# CAN_Optical.net
KiCad netlist of a schematic drawn in Altium Designer
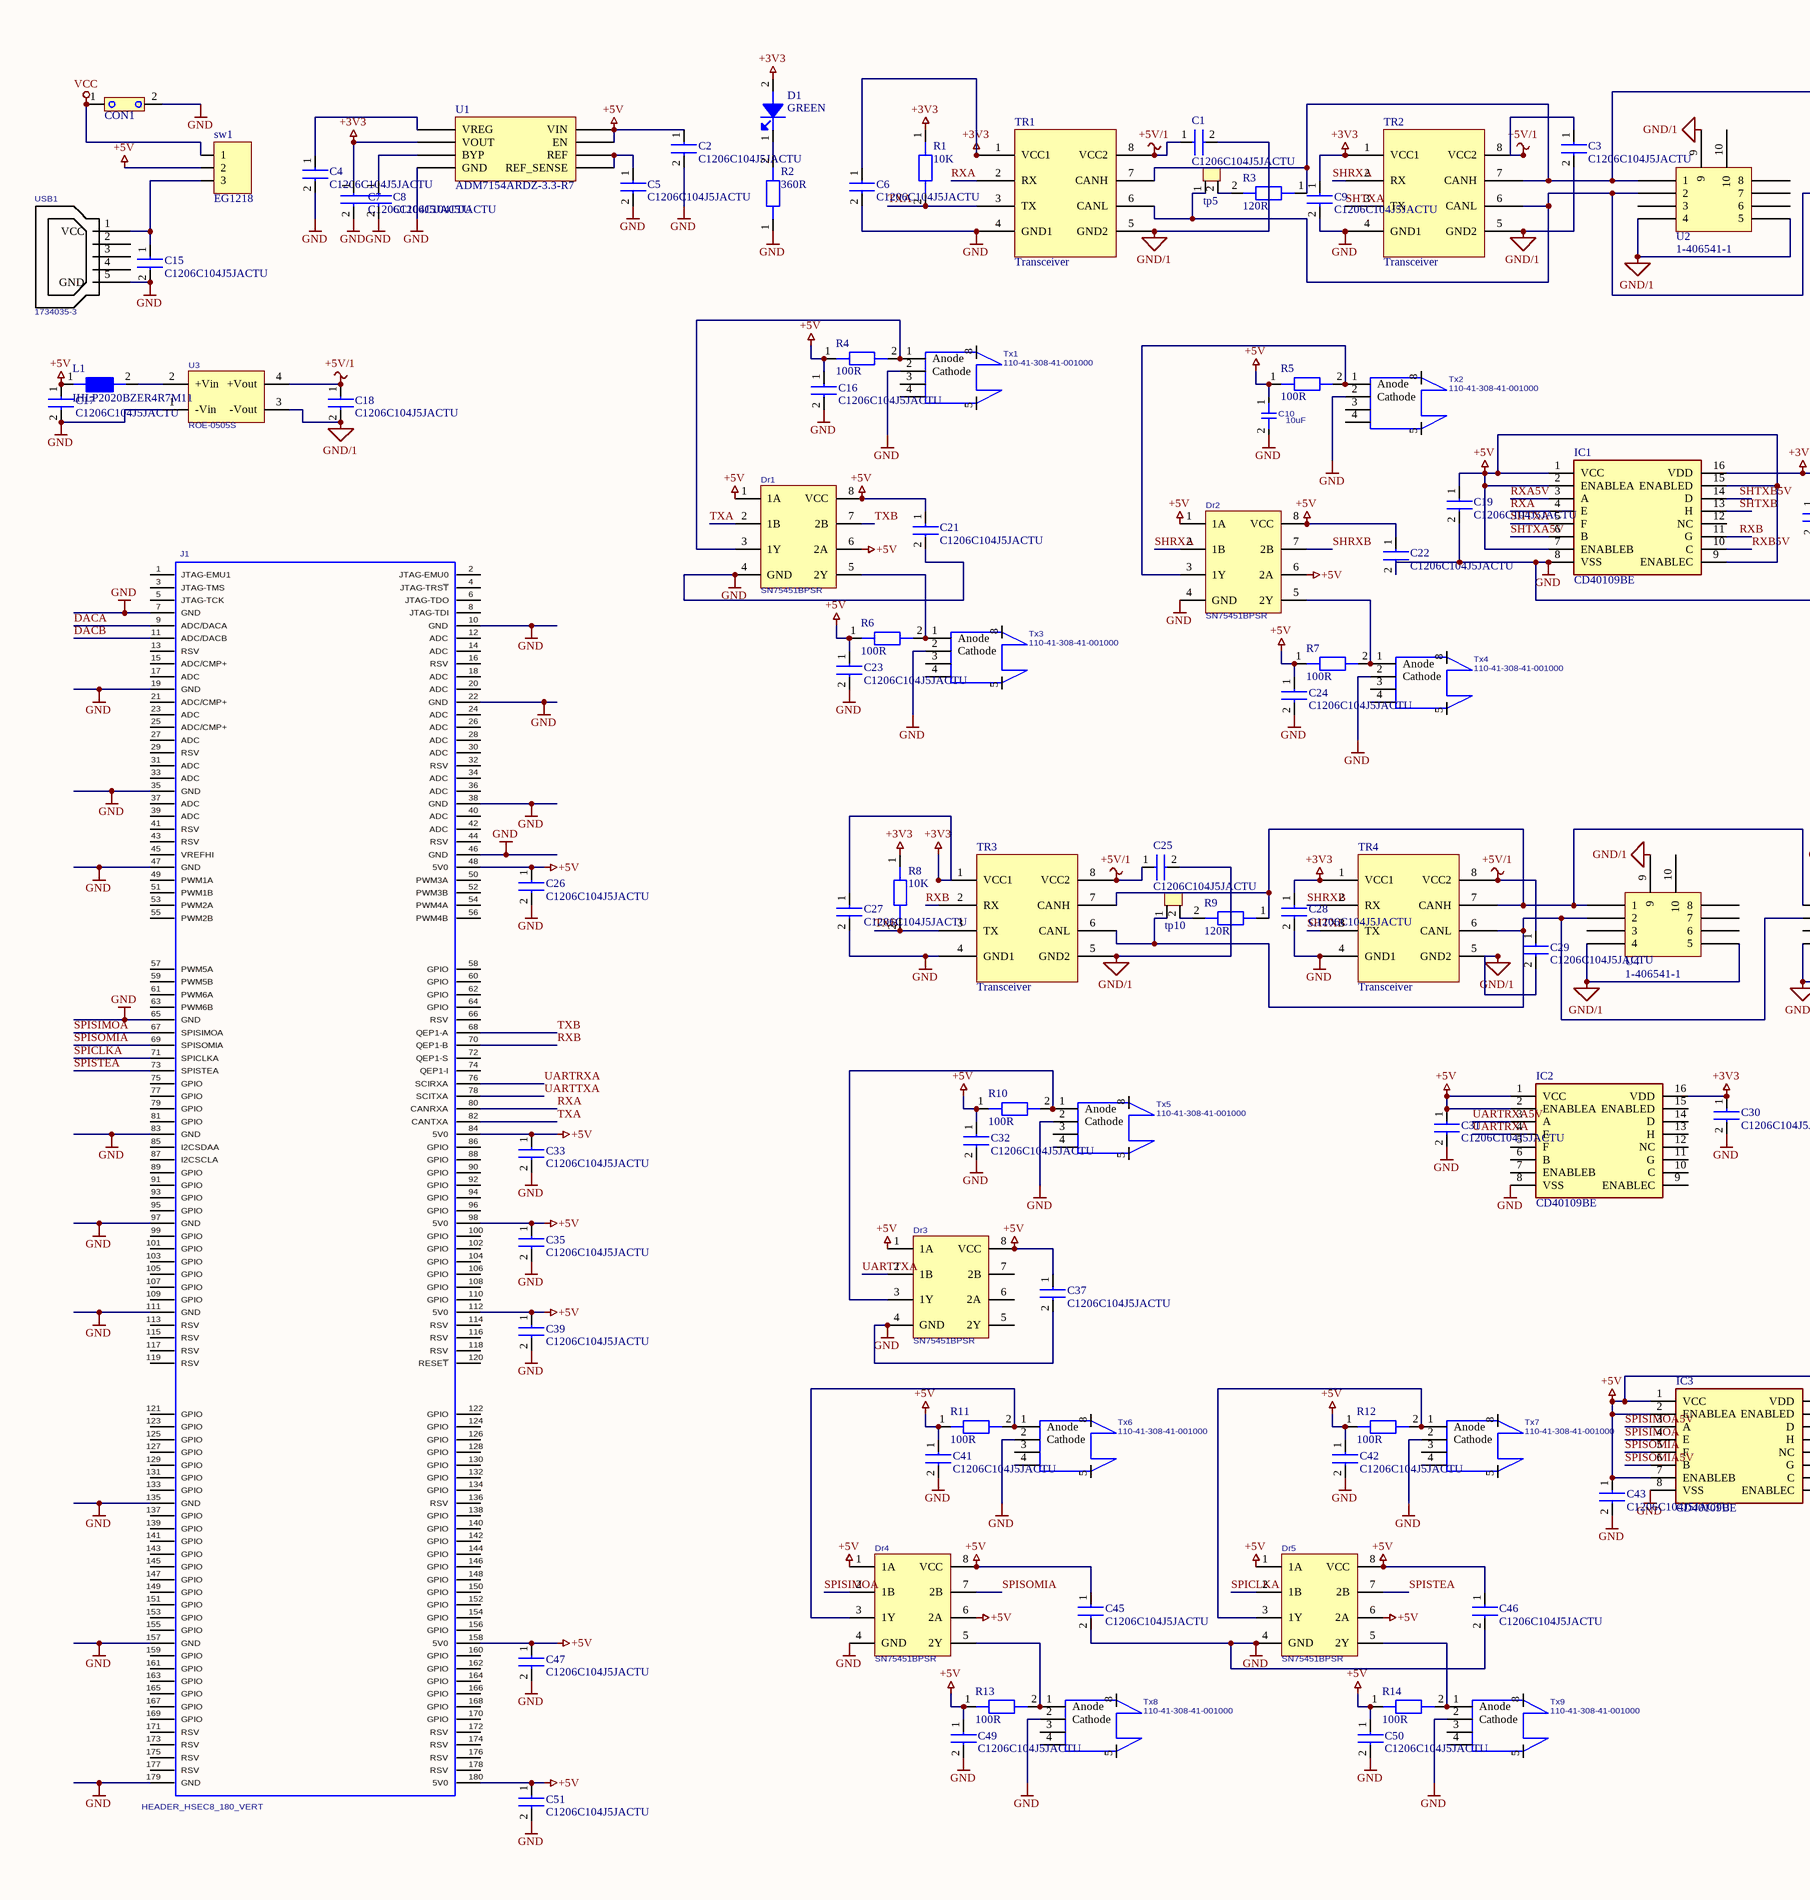
[diagram p0: CAN_Optical.SchDoc, left]
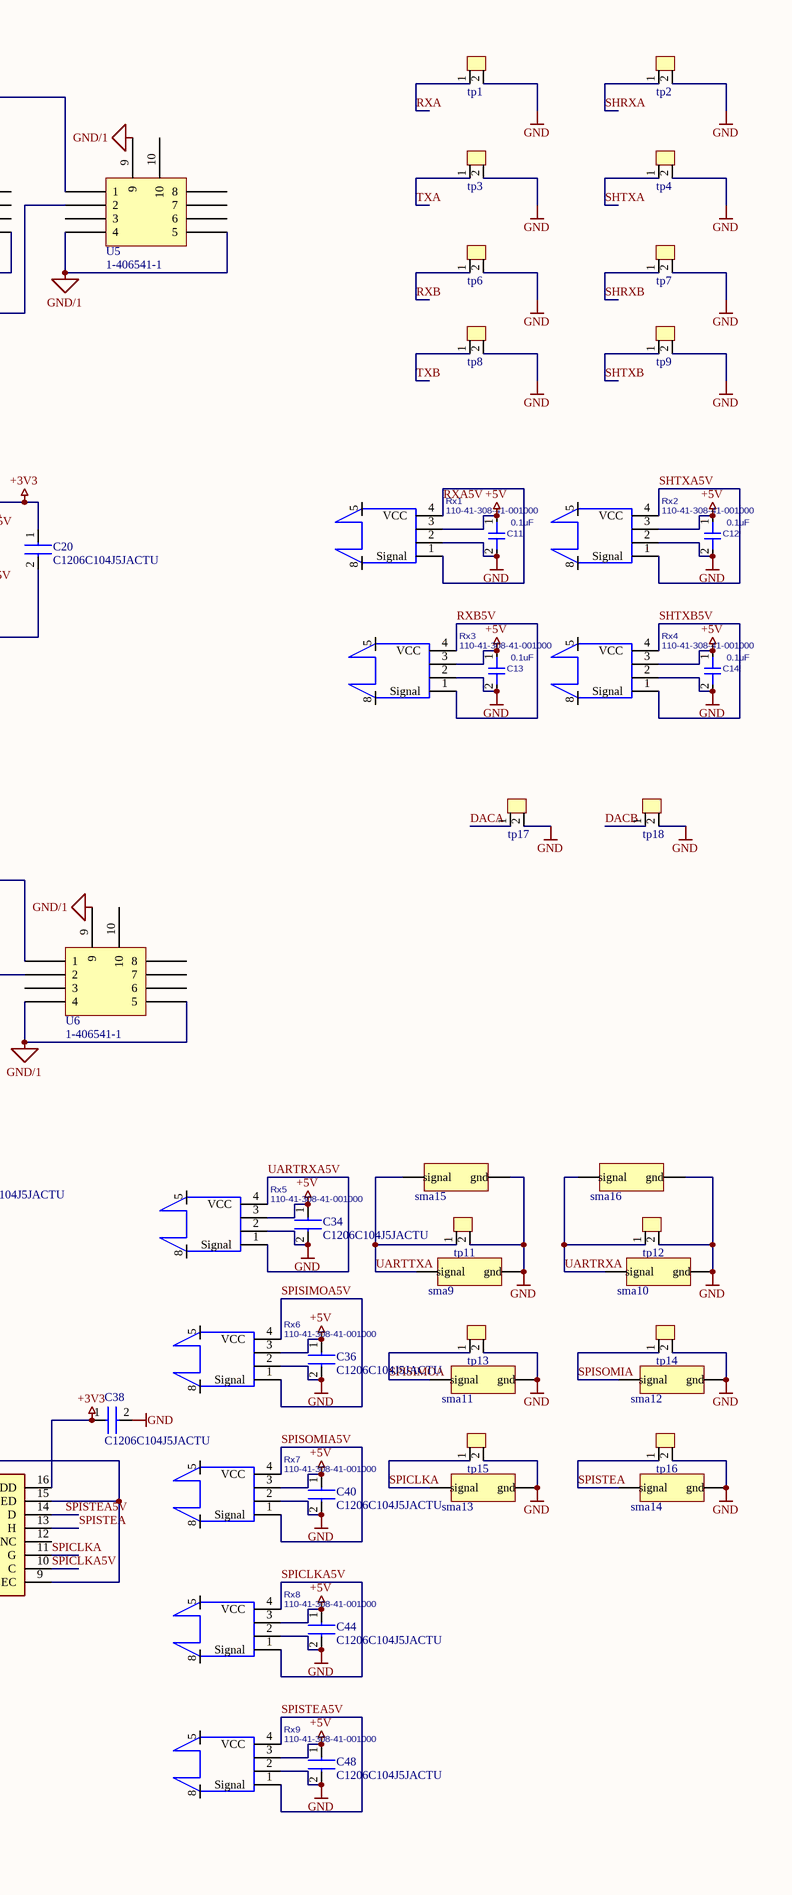
[diagram p1: CAN_Optical.SchDoc, right]

(export (version "E")
  (design (tool "Eeschema 10.0.6"))
  (components
    (comp (ref "C1")
      (value "C1206C104J5JACTU")
      (footprint "SamacSys:CAPC3216X135N")
      (description "Capacitor")
      (libsource (lib "CAN_Optical_SchLib") (part "C1206C104J5JACTU"))
    )
    (comp (ref "C2")
      (value "C1206C104J5JACTU")
      (footprint "SamacSys:CAPC3216X135N")
      (description "Capacitor")
      (libsource (lib "CAN_Optical_SchLib") (part "C1206C104J5JACTU"))
    )
    (comp (ref "C3")
      (value "C1206C104J5JACTU")
      (footprint "SamacSys:CAPC3216X135N")
      (description "Capacitor")
      (libsource (lib "CAN_Optical_SchLib") (part "C1206C104J5JACTU"))
    )
    (comp (ref "C4")
      (value "C1206C104J5JACTU")
      (footprint "SamacSys:CAPC3216X135N")
      (description "Capacitor")
      (libsource (lib "CAN_Optical_SchLib") (part "C1206C104J5JACTU"))
    )
    (comp (ref "C5")
      (value "C1206C104J5JACTU")
      (footprint "SamacSys:CAPC3216X135N")
      (description "Capacitor")
      (libsource (lib "CAN_Optical_SchLib") (part "C1206C104J5JACTU"))
    )
    (comp (ref "C6")
      (value "C1206C104J5JACTU")
      (footprint "SamacSys:CAPC3216X135N")
      (description "Capacitor")
      (libsource (lib "CAN_Optical_SchLib") (part "C1206C104J5JACTU"))
    )
    (comp (ref "C7")
      (value "C1206C104J5JACTU")
      (footprint "SamacSys:CAPC3216X135N")
      (description "Capacitor")
      (libsource (lib "CAN_Optical_SchLib") (part "C1206C104J5JACTU"))
    )
    (comp (ref "C8")
      (value "C1206C104J5JACTU")
      (footprint "SamacSys:CAPC3216X135N")
      (description "Capacitor")
      (libsource (lib "CAN_Optical_SchLib") (part "C1206C104J5JACTU"))
    )
    (comp (ref "C9")
      (value "C1206C104J5JACTU")
      (footprint "SamacSys:CAPC3216X135N")
      (description "Capacitor")
      (libsource (lib "CAN_Optical_SchLib") (part "C1206C104J5JACTU"))
    )
    (comp (ref "C10")
      (value "10uF")
      (footprint "CAPC3216X135N")
      (fields
        (field (name "MANUFACTURER") "KEMET")
        (field (name "MANUFACTURER PART NUMBER") "C0603C104K8RACTU")
        (field (name "TOLERANCE") "10%")
      )
      (libsource (lib "CAN_Optical_SchLib") (part "C0603C104K8RACTU"))
    )
    (comp (ref "C11")
      (value "0.1uF")
      (footprint "CAPC3216X135N")
      (fields
        (field (name "MANUFACTURER") "KEMET")
        (field (name "MANUFACTURER PART NUMBER") "C0603C104K8RACTU")
        (field (name "TOLERANCE") "10%")
      )
      (libsource (lib "CAN_Optical_SchLib") (part "C0603C104K8RACTU"))
    )
    (comp (ref "C12")
      (value "0.1uF")
      (footprint "CAPC3216X135N")
      (fields
        (field (name "MANUFACTURER") "KEMET")
        (field (name "MANUFACTURER PART NUMBER") "C0603C104K8RACTU")
        (field (name "TOLERANCE") "10%")
      )
      (libsource (lib "CAN_Optical_SchLib") (part "C0603C104K8RACTU"))
    )
    (comp (ref "C13")
      (value "0.1uF")
      (footprint "CAPC3216X135N")
      (fields
        (field (name "MANUFACTURER") "KEMET")
        (field (name "MANUFACTURER PART NUMBER") "C0603C104K8RACTU")
        (field (name "TOLERANCE") "10%")
      )
      (libsource (lib "CAN_Optical_SchLib") (part "C0603C104K8RACTU"))
    )
    (comp (ref "C14")
      (value "0.1uF")
      (footprint "CAPC3216X135N")
      (fields
        (field (name "MANUFACTURER") "KEMET")
        (field (name "MANUFACTURER PART NUMBER") "C0603C104K8RACTU")
        (field (name "TOLERANCE") "10%")
      )
      (libsource (lib "CAN_Optical_SchLib") (part "C0603C104K8RACTU"))
    )
    (comp (ref "C15")
      (value "C1206C104J5JACTU")
      (footprint "SamacSys:CAPC3216X135N")
      (description "Capacitor")
      (libsource (lib "CAN_Optical_SchLib") (part "C1206C104J5JACTU"))
    )
    (comp (ref "C16")
      (value "C1206C104J5JACTU")
      (footprint "SamacSys:CAPC3216X135N")
      (description "Capacitor")
      (libsource (lib "CAN_Optical_SchLib") (part "C1206C104J5JACTU"))
    )
    (comp (ref "C17")
      (value "C1206C104J5JACTU")
      (footprint "SamacSys:CAPC3216X135N")
      (description "Capacitor")
      (libsource (lib "CAN_Optical_SchLib") (part "C1206C104J5JACTU"))
    )
    (comp (ref "C18")
      (value "C1206C104J5JACTU")
      (footprint "SamacSys:CAPC3216X135N")
      (description "Capacitor")
      (libsource (lib "CAN_Optical_SchLib") (part "C1206C104J5JACTU"))
    )
    (comp (ref "C19")
      (value "C1206C104J5JACTU")
      (footprint "SamacSys:CAPC3216X135N")
      (description "Capacitor")
      (libsource (lib "CAN_Optical_SchLib") (part "C1206C104J5JACTU"))
    )
    (comp (ref "C20")
      (value "C1206C104J5JACTU")
      (footprint "SamacSys:CAPC3216X135N")
      (description "Capacitor")
      (libsource (lib "CAN_Optical_SchLib") (part "C1206C104J5JACTU"))
    )
    (comp (ref "C21")
      (value "C1206C104J5JACTU")
      (footprint "SamacSys:CAPC3216X135N")
      (description "Capacitor")
      (libsource (lib "CAN_Optical_SchLib") (part "C1206C104J5JACTU"))
    )
    (comp (ref "C22")
      (value "C1206C104J5JACTU")
      (footprint "SamacSys:CAPC3216X135N")
      (description "Capacitor")
      (libsource (lib "CAN_Optical_SchLib") (part "C1206C104J5JACTU"))
    )
    (comp (ref "C23")
      (value "C1206C104J5JACTU")
      (footprint "SamacSys:CAPC3216X135N")
      (description "Capacitor")
      (libsource (lib "CAN_Optical_SchLib") (part "C1206C104J5JACTU"))
    )
    (comp (ref "C24")
      (value "C1206C104J5JACTU")
      (footprint "SamacSys:CAPC3216X135N")
      (description "Capacitor")
      (libsource (lib "CAN_Optical_SchLib") (part "C1206C104J5JACTU"))
    )
    (comp (ref "C25")
      (value "C1206C104J5JACTU")
      (footprint "SamacSys:CAPC3216X135N")
      (description "Capacitor")
      (libsource (lib "CAN_Optical_SchLib") (part "C1206C104J5JACTU"))
    )
    (comp (ref "C26")
      (value "C1206C104J5JACTU")
      (footprint "SamacSys:CAPC3216X135N")
      (description "Capacitor")
      (libsource (lib "CAN_Optical_SchLib") (part "C1206C104J5JACTU"))
    )
    (comp (ref "C27")
      (value "C1206C104J5JACTU")
      (footprint "SamacSys:CAPC3216X135N")
      (description "Capacitor")
      (libsource (lib "CAN_Optical_SchLib") (part "C1206C104J5JACTU"))
    )
    (comp (ref "C28")
      (value "C1206C104J5JACTU")
      (footprint "SamacSys:CAPC3216X135N")
      (description "Capacitor")
      (libsource (lib "CAN_Optical_SchLib") (part "C1206C104J5JACTU"))
    )
    (comp (ref "C29")
      (value "C1206C104J5JACTU")
      (footprint "SamacSys:CAPC3216X135N")
      (description "Capacitor")
      (libsource (lib "CAN_Optical_SchLib") (part "C1206C104J5JACTU"))
    )
    (comp (ref "C30")
      (value "C1206C104J5JACTU")
      (footprint "SamacSys:CAPC3216X135N")
      (description "Capacitor")
      (libsource (lib "CAN_Optical_SchLib") (part "C1206C104J5JACTU"))
    )
    (comp (ref "C31")
      (value "C1206C104J5JACTU")
      (footprint "SamacSys:CAPC3216X135N")
      (description "Capacitor")
      (libsource (lib "CAN_Optical_SchLib") (part "C1206C104J5JACTU"))
    )
    (comp (ref "C32")
      (value "C1206C104J5JACTU")
      (footprint "SamacSys:CAPC3216X135N")
      (description "Capacitor")
      (libsource (lib "CAN_Optical_SchLib") (part "C1206C104J5JACTU"))
    )
    (comp (ref "C33")
      (value "C1206C104J5JACTU")
      (footprint "SamacSys:CAPC3216X135N")
      (description "Capacitor")
      (libsource (lib "CAN_Optical_SchLib") (part "C1206C104J5JACTU"))
    )
    (comp (ref "C34")
      (value "C1206C104J5JACTU")
      (footprint "SamacSys:CAPC3216X135N")
      (description "Capacitor")
      (libsource (lib "CAN_Optical_SchLib") (part "C1206C104J5JACTU"))
    )
    (comp (ref "C35")
      (value "C1206C104J5JACTU")
      (footprint "SamacSys:CAPC3216X135N")
      (description "Capacitor")
      (libsource (lib "CAN_Optical_SchLib") (part "C1206C104J5JACTU"))
    )
    (comp (ref "C36")
      (value "C1206C104J5JACTU")
      (footprint "SamacSys:CAPC3216X135N")
      (description "Capacitor")
      (libsource (lib "CAN_Optical_SchLib") (part "C1206C104J5JACTU"))
    )
    (comp (ref "C37")
      (value "C1206C104J5JACTU")
      (footprint "SamacSys:CAPC3216X135N")
      (description "Capacitor")
      (libsource (lib "CAN_Optical_SchLib") (part "C1206C104J5JACTU"))
    )
    (comp (ref "C38")
      (value "C1206C104J5JACTU")
      (footprint "SamacSys:CAPC3216X135N")
      (description "Capacitor")
      (libsource (lib "CAN_Optical_SchLib") (part "C1206C104J5JACTU"))
    )
    (comp (ref "C39")
      (value "C1206C104J5JACTU")
      (footprint "SamacSys:CAPC3216X135N")
      (description "Capacitor")
      (libsource (lib "CAN_Optical_SchLib") (part "C1206C104J5JACTU"))
    )
    (comp (ref "C40")
      (value "C1206C104J5JACTU")
      (footprint "SamacSys:CAPC3216X135N")
      (description "Capacitor")
      (libsource (lib "CAN_Optical_SchLib") (part "C1206C104J5JACTU"))
    )
    (comp (ref "C41")
      (value "C1206C104J5JACTU")
      (footprint "SamacSys:CAPC3216X135N")
      (description "Capacitor")
      (libsource (lib "CAN_Optical_SchLib") (part "C1206C104J5JACTU"))
    )
    (comp (ref "C42")
      (value "C1206C104J5JACTU")
      (footprint "SamacSys:CAPC3216X135N")
      (description "Capacitor")
      (libsource (lib "CAN_Optical_SchLib") (part "C1206C104J5JACTU"))
    )
    (comp (ref "C43")
      (value "C1206C104J5JACTU")
      (footprint "SamacSys:CAPC3216X135N")
      (description "Capacitor")
      (libsource (lib "CAN_Optical_SchLib") (part "C1206C104J5JACTU"))
    )
    (comp (ref "C44")
      (value "C1206C104J5JACTU")
      (footprint "SamacSys:CAPC3216X135N")
      (description "Capacitor")
      (libsource (lib "CAN_Optical_SchLib") (part "C1206C104J5JACTU"))
    )
    (comp (ref "C45")
      (value "C1206C104J5JACTU")
      (footprint "SamacSys:CAPC3216X135N")
      (description "Capacitor")
      (libsource (lib "CAN_Optical_SchLib") (part "C1206C104J5JACTU"))
    )
    (comp (ref "C46")
      (value "C1206C104J5JACTU")
      (footprint "SamacSys:CAPC3216X135N")
      (description "Capacitor")
      (libsource (lib "CAN_Optical_SchLib") (part "C1206C104J5JACTU"))
    )
    (comp (ref "C47")
      (value "C1206C104J5JACTU")
      (footprint "SamacSys:CAPC3216X135N")
      (description "Capacitor")
      (libsource (lib "CAN_Optical_SchLib") (part "C1206C104J5JACTU"))
    )
    (comp (ref "C48")
      (value "C1206C104J5JACTU")
      (footprint "SamacSys:CAPC3216X135N")
      (description "Capacitor")
      (libsource (lib "CAN_Optical_SchLib") (part "C1206C104J5JACTU"))
    )
    (comp (ref "C49")
      (value "C1206C104J5JACTU")
      (footprint "SamacSys:CAPC3216X135N")
      (description "Capacitor")
      (libsource (lib "CAN_Optical_SchLib") (part "C1206C104J5JACTU"))
    )
    (comp (ref "C50")
      (value "C1206C104J5JACTU")
      (footprint "SamacSys:CAPC3216X135N")
      (description "Capacitor")
      (libsource (lib "CAN_Optical_SchLib") (part "C1206C104J5JACTU"))
    )
    (comp (ref "C51")
      (value "C1206C104J5JACTU")
      (footprint "SamacSys:CAPC3216X135N")
      (description "Capacitor")
      (libsource (lib "CAN_Optical_SchLib") (part "C1206C104J5JACTU"))
    )
    (comp (ref "CON1")
      (value "ED700/2")
      (footprint "ED700/2")
      (fields (field (name "DIGI-KEY PART NUMBER") "ED1631-ND"))
      (libsource (lib "CAN_Optical_SchLib") (part "ED700/2"))
    )
    (comp (ref "D1")
      (value "GREEN")
      (footprint "LED0603G")
      (fields (field (name "TOLERANCE") "1%"))
      (libsource (lib "CAN_Optical_SchLib") (part "ERJ-3EKF8062V"))
    )
    (comp (ref "Dr1")
      (value "SN75451BPSR")
      (footprint "SN75451BPS")
      (description "IC DUAL PERIPHERAL DRVR 8-SOP")
      (fields (field (name "MANUFACTURER") "Texas Instruments"))
      (libsource (lib "CAN_Optical_SchLib") (part "SN75451BPSRG4"))
    )
    (comp (ref "Dr2")
      (value "SN75451BPSR")
      (footprint "SN75451BPS")
      (description "IC DUAL PERIPHERAL DRVR 8-SOP")
      (fields (field (name "MANUFACTURER") "Texas Instruments"))
      (libsource (lib "CAN_Optical_SchLib") (part "SN75451BPSR"))
    )
    (comp (ref "Dr3")
      (value "SN75451BPSR")
      (footprint "SN75451BPS")
      (description "IC DUAL PERIPHERAL DRVR 8-SOP")
      (fields (field (name "MANUFACTURER") "Texas Instruments"))
      (libsource (lib "CAN_Optical_SchLib") (part "SN75451BPSRG4"))
    )
    (comp (ref "Dr4")
      (value "SN75451BPSR")
      (footprint "SN75451BPS")
      (description "IC DUAL PERIPHERAL DRVR 8-SOP")
      (fields (field (name "MANUFACTURER") "Texas Instruments"))
      (libsource (lib "CAN_Optical_SchLib") (part "SN75451BPSRG4"))
    )
    (comp (ref "Dr5")
      (value "SN75451BPSR")
      (footprint "SN75451BPS")
      (description "IC DUAL PERIPHERAL DRVR 8-SOP")
      (fields (field (name "MANUFACTURER") "Texas Instruments"))
      (libsource (lib "CAN_Optical_SchLib") (part "SN75451BPSRG4"))
    )
    (comp (ref "IC1")
      (value "CD40109BE")
      (footprint "SamacSys:DIP794W53P254L1930H508Q16N")
      (description "Integrated Circuit")
      (fields (field (name "MOUSER2 PART NUMBER") "595-CD40109BE"))
      (libsource (lib "CAN_Optical_SchLib") (part "CD40109BE"))
    )
    (comp (ref "IC2")
      (value "CD40109BE")
      (footprint "SamacSys:DIP794W53P254L1930H508Q16N")
      (description "Integrated Circuit")
      (fields (field (name "MOUSER2 PART NUMBER") "595-CD40109BE"))
      (libsource (lib "CAN_Optical_SchLib") (part "CD40109BE"))
    )
    (comp (ref "IC3")
      (value "CD40109BE")
      (footprint "SamacSys:DIP794W53P254L1930H508Q16N")
      (description "Integrated Circuit")
      (fields (field (name "MOUSER2 PART NUMBER") "595-CD40109BE"))
      (libsource (lib "CAN_Optical_SchLib") (part "CD40109BE"))
    )
    (comp (ref "J1")
      (value "HEADER_HSEC8_180_VERT")
      (footprint "HEADER_HSEC8_180_DV")
      (description "180 pin (120 + 60) HSEC8 socket, samtec")
      (fields (field (name "DIGI-KEY PART NUMBER") "SAM9083-ND & SAM9080-ND"))
      (libsource (lib "CAN_Optical_SchLib") (part "HEADER_HSEC8_180_VERT"))
    )
    (comp (ref "L1")
      (value "IHLP2020BZER4R7M11")
      (footprint "L_IHLP2020BZER4R7M11")
      (description "FIXED IND 4.7UH 3.2A 81.3 MOHM")
      (fields (field (name "MANUFACTURER") "Vishay Dale") (field (name "TOLERANCE") "20%"))
      (libsource (lib "CAN_Optical_SchLib") (part "IHLP2020BZER4R7M11"))
    )
    (comp (ref "R1")
      (value "10K")
      (footprint "R0805 - duplicate - duplicate")
      (description "Res Thick Film 0805 360 Ohm 1% 0.125W(1/8W) ±100ppm/C Molded SMD Automotive Paper T/R")
      (fields (field (name "TOLERANCE") "1%"))
      (libsource (lib "CAN_Optical_SchLib") (part "CRCW0805360RFKEA"))
    )
    (comp (ref "R2")
      (value "360R")
      (footprint "R0805 - duplicate - duplicate")
      (description "Res Thick Film 0805 360 Ohm 1% 0.125W(1/8W) ±100ppm/C Molded SMD Automotive Paper T/R")
      (fields (field (name "TOLERANCE") "1%"))
      (libsource (lib "CAN_Optical_SchLib") (part "CRCW0805360RFKEA"))
    )
    (comp (ref "R3")
      (value "120R")
      (footprint "R0805 - duplicate - duplicate")
      (description "Res Thick Film 0805 360 Ohm 1% 0.125W(1/8W) ±100ppm/C Molded SMD Automotive Paper T/R")
      (fields (field (name "TOLERANCE") "1%"))
      (libsource (lib "CAN_Optical_SchLib") (part "CRCW0805360RFKEA"))
    )
    (comp (ref "R4")
      (value "100R")
      (footprint "R0805 - duplicate - duplicate")
      (description "Res Thick Film 0805 360 Ohm 1% 0.125W(1/8W) ±100ppm/C Molded SMD Automotive Paper T/R")
      (fields (field (name "TOLERANCE") "1%"))
      (libsource (lib "CAN_Optical_SchLib") (part "CRCW0805360RFKEA"))
    )
    (comp (ref "R5")
      (value "100R")
      (footprint "R0805 - duplicate - duplicate")
      (description "Res Thick Film 0805 360 Ohm 1% 0.125W(1/8W) ±100ppm/C Molded SMD Automotive Paper T/R")
      (fields (field (name "TOLERANCE") "1%"))
      (libsource (lib "CAN_Optical_SchLib") (part "CRCW0805360RFKEA"))
    )
    (comp (ref "R6")
      (value "100R")
      (footprint "R0805 - duplicate - duplicate")
      (description "Res Thick Film 0805 360 Ohm 1% 0.125W(1/8W) ±100ppm/C Molded SMD Automotive Paper T/R")
      (fields (field (name "TOLERANCE") "1%"))
      (libsource (lib "CAN_Optical_SchLib") (part "CRCW0805360RFKEA"))
    )
    (comp (ref "R7")
      (value "100R")
      (footprint "R0805 - duplicate - duplicate")
      (description "Res Thick Film 0805 360 Ohm 1% 0.125W(1/8W) ±100ppm/C Molded SMD Automotive Paper T/R")
      (fields (field (name "TOLERANCE") "1%"))
      (libsource (lib "CAN_Optical_SchLib") (part "CRCW0805360RFKEA"))
    )
    (comp (ref "R8")
      (value "10K")
      (footprint "R0805 - duplicate - duplicate")
      (description "Res Thick Film 0805 360 Ohm 1% 0.125W(1/8W) ±100ppm/C Molded SMD Automotive Paper T/R")
      (fields (field (name "TOLERANCE") "1%"))
      (libsource (lib "CAN_Optical_SchLib") (part "CRCW0805360RFKEA"))
    )
    (comp (ref "R9")
      (value "120R")
      (footprint "R0805 - duplicate - duplicate")
      (description "Res Thick Film 0805 360 Ohm 1% 0.125W(1/8W) ±100ppm/C Molded SMD Automotive Paper T/R")
      (fields (field (name "TOLERANCE") "1%"))
      (libsource (lib "CAN_Optical_SchLib") (part "CRCW0805360RFKEA"))
    )
    (comp (ref "R10")
      (value "100R")
      (footprint "R0805 - duplicate - duplicate")
      (description "Res Thick Film 0805 360 Ohm 1% 0.125W(1/8W) ±100ppm/C Molded SMD Automotive Paper T/R")
      (fields (field (name "TOLERANCE") "1%"))
      (libsource (lib "CAN_Optical_SchLib") (part "CRCW0805360RFKEA"))
    )
    (comp (ref "R11")
      (value "100R")
      (footprint "R0805 - duplicate - duplicate")
      (description "Res Thick Film 0805 360 Ohm 1% 0.125W(1/8W) ±100ppm/C Molded SMD Automotive Paper T/R")
      (fields (field (name "TOLERANCE") "1%"))
      (libsource (lib "CAN_Optical_SchLib") (part "CRCW0805360RFKEA"))
    )
    (comp (ref "R12")
      (value "100R")
      (footprint "R0805 - duplicate - duplicate")
      (description "Res Thick Film 0805 360 Ohm 1% 0.125W(1/8W) ±100ppm/C Molded SMD Automotive Paper T/R")
      (fields (field (name "TOLERANCE") "1%"))
      (libsource (lib "CAN_Optical_SchLib") (part "CRCW0805360RFKEA"))
    )
    (comp (ref "R13")
      (value "100R")
      (footprint "R0805 - duplicate - duplicate")
      (description "Res Thick Film 0805 360 Ohm 1% 0.125W(1/8W) ±100ppm/C Molded SMD Automotive Paper T/R")
      (fields (field (name "TOLERANCE") "1%"))
      (libsource (lib "CAN_Optical_SchLib") (part "CRCW0805360RFKEA"))
    )
    (comp (ref "R14")
      (value "100R")
      (footprint "R0805 - duplicate - duplicate")
      (description "Res Thick Film 0805 360 Ohm 1% 0.125W(1/8W) ±100ppm/C Molded SMD Automotive Paper T/R")
      (fields (field (name "TOLERANCE") "1%"))
      (libsource (lib "CAN_Optical_SchLib") (part "CRCW0805360RFKEA"))
    )
    (comp (ref "Rx1")
      (value "110-41-308-41-001000")
      (footprint "HFBRX5XXZ")
      (description "IC & Component Sockets 8 PIN SKT 200u Sn")
      (fields (field (name "MANUFACTURER") "Broadcom"))
      (libsource (lib "CAN_Optical_SchLib") (part "HFBR-2521Z"))
    )
    (comp (ref "Rx2")
      (value "110-41-308-41-001000")
      (footprint "HFBRX5XXZ")
      (description "IC & Component Sockets 8 PIN SKT 200u Sn")
      (fields (field (name "MANUFACTURER") "Broadcom"))
      (libsource (lib "CAN_Optical_SchLib") (part "HFBR-2521Z"))
    )
    (comp (ref "Rx3")
      (value "110-41-308-41-001000")
      (footprint "HFBRX5XXZ")
      (description "IC & Component Sockets 8 PIN SKT 200u Sn")
      (fields (field (name "MANUFACTURER") "Broadcom"))
      (libsource (lib "CAN_Optical_SchLib") (part "HFBR-2521Z"))
    )
    (comp (ref "Rx4")
      (value "110-41-308-41-001000")
      (footprint "HFBRX5XXZ")
      (description "IC & Component Sockets 8 PIN SKT 200u Sn")
      (fields (field (name "MANUFACTURER") "Broadcom"))
      (libsource (lib "CAN_Optical_SchLib") (part "HFBR-2521Z"))
    )
    (comp (ref "Rx5")
      (value "110-41-308-41-001000")
      (footprint "HFBRX5XXZ")
      (description "IC & Component Sockets 8 PIN SKT 200u Sn")
      (fields (field (name "MANUFACTURER") "Broadcom"))
      (libsource (lib "CAN_Optical_SchLib") (part "HFBR-2521Z"))
    )
    (comp (ref "Rx6")
      (value "110-41-308-41-001000")
      (footprint "HFBRX5XXZ")
      (description "IC & Component Sockets 8 PIN SKT 200u Sn")
      (fields (field (name "MANUFACTURER") "Broadcom"))
      (libsource (lib "CAN_Optical_SchLib") (part "HFBR-2521Z"))
    )
    (comp (ref "Rx7")
      (value "110-41-308-41-001000")
      (footprint "HFBRX5XXZ")
      (description "IC & Component Sockets 8 PIN SKT 200u Sn")
      (fields (field (name "MANUFACTURER") "Broadcom"))
      (libsource (lib "CAN_Optical_SchLib") (part "HFBR-2521Z"))
    )
    (comp (ref "Rx8")
      (value "110-41-308-41-001000")
      (footprint "HFBRX5XXZ")
      (description "IC & Component Sockets 8 PIN SKT 200u Sn")
      (fields (field (name "MANUFACTURER") "Broadcom"))
      (libsource (lib "CAN_Optical_SchLib") (part "HFBR-2521Z"))
    )
    (comp (ref "Rx9")
      (value "110-41-308-41-001000")
      (footprint "HFBRX5XXZ")
      (description "IC & Component Sockets 8 PIN SKT 200u Sn")
      (fields (field (name "MANUFACTURER") "Broadcom"))
      (libsource (lib "CAN_Optical_SchLib") (part "HFBR-2521Z"))
    )
    (comp (ref "sma9")
      (value "142-0701-201")
      (footprint "142-0701-201")
      (fields (field (name "DIGI-KEY PART NUMBER") "J500-ND"))
      (libsource (lib "CAN_Optical_SchLib") (part "142-0701-201"))
    )
    (comp (ref "sma10")
      (value "142-0701-201")
      (footprint "142-0701-201")
      (fields (field (name "DIGI-KEY PART NUMBER") "J500-ND"))
      (libsource (lib "CAN_Optical_SchLib") (part "142-0701-201"))
    )
    (comp (ref "sma11")
      (value "142-0701-201")
      (footprint "142-0701-201")
      (fields (field (name "DIGI-KEY PART NUMBER") "J500-ND"))
      (libsource (lib "CAN_Optical_SchLib") (part "142-0701-201"))
    )
    (comp (ref "sma12")
      (value "142-0701-201")
      (footprint "142-0701-201")
      (fields (field (name "DIGI-KEY PART NUMBER") "J500-ND"))
      (libsource (lib "CAN_Optical_SchLib") (part "142-0701-201"))
    )
    (comp (ref "sma13")
      (value "142-0701-201")
      (footprint "142-0701-201")
      (fields (field (name "DIGI-KEY PART NUMBER") "J500-ND"))
      (libsource (lib "CAN_Optical_SchLib") (part "142-0701-201"))
    )
    (comp (ref "sma14")
      (value "142-0701-201")
      (footprint "142-0701-201")
      (fields (field (name "DIGI-KEY PART NUMBER") "J500-ND"))
      (libsource (lib "CAN_Optical_SchLib") (part "142-0701-201"))
    )
    (comp (ref "sma15")
      (value "142-0701-201")
      (footprint "142-0701-201")
      (fields (field (name "DIGI-KEY PART NUMBER") "J500-ND"))
      (libsource (lib "CAN_Optical_SchLib") (part "142-0701-201"))
    )
    (comp (ref "sma16")
      (value "142-0701-201")
      (footprint "142-0701-201")
      (fields (field (name "DIGI-KEY PART NUMBER") "J500-ND"))
      (libsource (lib "CAN_Optical_SchLib") (part "142-0701-201"))
    )
    (comp (ref "sw1")
      (value "EG1218")
      (footprint "EG1218")
      (fields (field (name "DIGI-KEY PART NUMBER") "EG1903-ND"))
      (libsource (lib "CAN_Optical_SchLib") (part "EG1218"))
    )
    (comp (ref "tp1")
      (value "tp2")
      (footprint "tp2")
      (fields (field (name "DIGI-KEY PART NUMBER") "S1012EC-10-ND"))
      (libsource (lib "CAN_Optical_SchLib") (part "tp2"))
    )
    (comp (ref "tp2")
      (value "tp2")
      (footprint "tp2")
      (fields (field (name "DIGI-KEY PART NUMBER") "S1012EC-10-ND"))
      (libsource (lib "CAN_Optical_SchLib") (part "tp2"))
    )
    (comp (ref "tp3")
      (value "tp2")
      (footprint "tp2")
      (fields (field (name "DIGI-KEY PART NUMBER") "S1012EC-10-ND"))
      (libsource (lib "CAN_Optical_SchLib") (part "tp2"))
    )
    (comp (ref "tp4")
      (value "tp2")
      (footprint "tp2")
      (fields (field (name "DIGI-KEY PART NUMBER") "S1012EC-10-ND"))
      (libsource (lib "CAN_Optical_SchLib") (part "tp2"))
    )
    (comp (ref "tp5")
      (value "tp2")
      (footprint "tp2")
      (fields (field (name "DIGI-KEY PART NUMBER") "S1012EC-10-ND"))
      (libsource (lib "CAN_Optical_SchLib") (part "tp2"))
    )
    (comp (ref "tp6")
      (value "tp2")
      (footprint "tp2")
      (fields (field (name "DIGI-KEY PART NUMBER") "S1012EC-10-ND"))
      (libsource (lib "CAN_Optical_SchLib") (part "tp2"))
    )
    (comp (ref "tp7")
      (value "tp2")
      (footprint "tp2")
      (fields (field (name "DIGI-KEY PART NUMBER") "S1012EC-10-ND"))
      (libsource (lib "CAN_Optical_SchLib") (part "tp2"))
    )
    (comp (ref "tp8")
      (value "tp2")
      (footprint "tp2")
      (fields (field (name "DIGI-KEY PART NUMBER") "S1012EC-10-ND"))
      (libsource (lib "CAN_Optical_SchLib") (part "tp2"))
    )
    (comp (ref "tp9")
      (value "tp2")
      (footprint "tp2")
      (fields (field (name "DIGI-KEY PART NUMBER") "S1012EC-10-ND"))
      (libsource (lib "CAN_Optical_SchLib") (part "tp2"))
    )
    (comp (ref "tp10")
      (value "tp2")
      (footprint "tp2")
      (fields (field (name "DIGI-KEY PART NUMBER") "S1012EC-10-ND"))
      (libsource (lib "CAN_Optical_SchLib") (part "tp2"))
    )
    (comp (ref "tp11")
      (value "tp2")
      (footprint "tp2")
      (fields (field (name "DIGI-KEY PART NUMBER") "S1012EC-10-ND"))
      (libsource (lib "CAN_Optical_SchLib") (part "tp2"))
    )
    (comp (ref "tp12")
      (value "tp2")
      (footprint "tp2")
      (fields (field (name "DIGI-KEY PART NUMBER") "S1012EC-10-ND"))
      (libsource (lib "CAN_Optical_SchLib") (part "tp2"))
    )
    (comp (ref "tp13")
      (value "tp2")
      (footprint "tp2")
      (fields (field (name "DIGI-KEY PART NUMBER") "S1012EC-10-ND"))
      (libsource (lib "CAN_Optical_SchLib") (part "tp2"))
    )
    (comp (ref "tp14")
      (value "tp2")
      (footprint "tp2")
      (fields (field (name "DIGI-KEY PART NUMBER") "S1012EC-10-ND"))
      (libsource (lib "CAN_Optical_SchLib") (part "tp2"))
    )
    (comp (ref "tp15")
      (value "tp2")
      (footprint "tp2")
      (fields (field (name "DIGI-KEY PART NUMBER") "S1012EC-10-ND"))
      (libsource (lib "CAN_Optical_SchLib") (part "tp2"))
    )
    (comp (ref "tp16")
      (value "tp2")
      (footprint "tp2")
      (fields (field (name "DIGI-KEY PART NUMBER") "S1012EC-10-ND"))
      (libsource (lib "CAN_Optical_SchLib") (part "tp2"))
    )
    (comp (ref "tp17")
      (value "tp2")
      (footprint "tp2")
      (fields (field (name "DIGI-KEY PART NUMBER") "S1012EC-10-ND"))
      (libsource (lib "CAN_Optical_SchLib") (part "tp2"))
    )
    (comp (ref "tp18")
      (value "tp2")
      (footprint "tp2")
      (fields (field (name "DIGI-KEY PART NUMBER") "S1012EC-10-ND"))
      (libsource (lib "CAN_Optical_SchLib") (part "tp2"))
    )
    (comp (ref "TR1")
      (value "Transceiver")
      (footprint "RXTX_ISO1050")
      (description "CAN 1Mbps 3.3V/5V 8-Pin SOP")
      (fields
        (field (name "MANUFACTURER") "Texas Instruments")
        (field (name "MANUFACTURER PART NUMBER") "ISO1050DUBR")
      )
      (libsource (lib "CAN_Optical_SchLib") (part "ISO1050DUBR"))
    )
    (comp (ref "TR2")
      (value "Transceiver")
      (footprint "RXTX_ISO1050")
      (description "CAN 1Mbps 3.3V/5V 8-Pin SOP")
      (fields
        (field (name "MANUFACTURER") "Texas Instruments")
        (field (name "MANUFACTURER PART NUMBER") "ISO1050DUBR")
      )
      (libsource (lib "CAN_Optical_SchLib") (part "ISO1050DUBR"))
    )
    (comp (ref "TR3")
      (value "Transceiver")
      (footprint "RXTX_ISO1050")
      (description "CAN 1Mbps 3.3V/5V 8-Pin SOP")
      (fields
        (field (name "MANUFACTURER") "Texas Instruments")
        (field (name "MANUFACTURER PART NUMBER") "ISO1050DUBR")
      )
      (libsource (lib "CAN_Optical_SchLib") (part "ISO1050DUBR"))
    )
    (comp (ref "TR4")
      (value "Transceiver")
      (footprint "RXTX_ISO1050")
      (description "CAN 1Mbps 3.3V/5V 8-Pin SOP")
      (fields
        (field (name "MANUFACTURER") "Texas Instruments")
        (field (name "MANUFACTURER PART NUMBER") "ISO1050DUBR")
      )
      (libsource (lib "CAN_Optical_SchLib") (part "ISO1050DUBR"))
    )
    (comp (ref "Tx1")
      (value "110-41-308-41-001000")
      (footprint "HFBRX5XXZ")
      (description "IC & Component Sockets 8 PIN SKT 200u Sn")
      (fields (field (name "MANUFACTURER") "Broadcom Avago"))
      (libsource (lib "CAN_Optical_SchLib") (part "HFBR-1527Z"))
    )
    (comp (ref "Tx2")
      (value "110-41-308-41-001000")
      (footprint "HFBRX5XXZ")
      (description "IC & Component Sockets 8 PIN SKT 200u Sn")
      (fields (field (name "MANUFACTURER") "Broadcom Avago"))
      (libsource (lib "CAN_Optical_SchLib") (part "HFBR-1527Z"))
    )
    (comp (ref "Tx3")
      (value "110-41-308-41-001000")
      (footprint "HFBRX5XXZ")
      (description "IC & Component Sockets 8 PIN SKT 200u Sn")
      (fields (field (name "MANUFACTURER") "Broadcom Avago"))
      (libsource (lib "CAN_Optical_SchLib") (part "HFBR-1527Z"))
    )
    (comp (ref "Tx4")
      (value "110-41-308-41-001000")
      (footprint "HFBRX5XXZ")
      (description "IC & Component Sockets 8 PIN SKT 200u Sn")
      (fields (field (name "MANUFACTURER") "Broadcom Avago"))
      (libsource (lib "CAN_Optical_SchLib") (part "HFBR-1527Z"))
    )
    (comp (ref "Tx5")
      (value "110-41-308-41-001000")
      (footprint "HFBRX5XXZ")
      (description "IC & Component Sockets 8 PIN SKT 200u Sn")
      (fields (field (name "MANUFACTURER") "Broadcom Avago"))
      (libsource (lib "CAN_Optical_SchLib") (part "HFBR-1527Z"))
    )
    (comp (ref "Tx6")
      (value "110-41-308-41-001000")
      (footprint "HFBRX5XXZ")
      (description "IC & Component Sockets 8 PIN SKT 200u Sn")
      (fields (field (name "MANUFACTURER") "Broadcom Avago"))
      (libsource (lib "CAN_Optical_SchLib") (part "HFBR-1527Z"))
    )
    (comp (ref "Tx7")
      (value "110-41-308-41-001000")
      (footprint "HFBRX5XXZ")
      (description "IC & Component Sockets 8 PIN SKT 200u Sn")
      (fields (field (name "MANUFACTURER") "Broadcom Avago"))
      (libsource (lib "CAN_Optical_SchLib") (part "HFBR-1527Z"))
    )
    (comp (ref "Tx8")
      (value "110-41-308-41-001000")
      (footprint "HFBRX5XXZ")
      (description "IC & Component Sockets 8 PIN SKT 200u Sn")
      (fields (field (name "MANUFACTURER") "Broadcom Avago"))
      (libsource (lib "CAN_Optical_SchLib") (part "HFBR-1527Z"))
    )
    (comp (ref "Tx9")
      (value "110-41-308-41-001000")
      (footprint "HFBRX5XXZ")
      (description "IC & Component Sockets 8 PIN SKT 200u Sn")
      (fields (field (name "MANUFACTURER") "Broadcom Avago"))
      (libsource (lib "CAN_Optical_SchLib") (part "HFBR-1527Z"))
    )
    (comp (ref "U1")
      (value "ADM7154ARDZ-3.3-R7")
      (footprint "ADM7154ARDZ-3.3-R7")
      (description "Linear Voltage Regulator IC Positive Fixed 1 Output 3.3V 600mA 8-SOIC-EP")
      (fields (field (name "DIGI-KEY PART NUMBER") "ADM7154ARDZ-3.3-R7CT-ND"))
      (libsource (lib "CAN_Optical_SchLib") (part "ADM7154ARDZ-3.3-R7"))
    )
    (comp (ref "U2")
      (value "1-406541-1")
      (footprint "1-406541-1")
      (fields (field (name "DIGI-KEY PART NUMBER") "A97716-ND"))
      (libsource (lib "CAN_Optical_SchLib") (part "1-406541-1"))
    )
    (comp (ref "U3")
      (value "ROE-0505S")
      (footprint "RECOM_DCDC")
      (description "Module DC-DC 5VIN 1-OUT 5V 0.2A 1W 4-Pin SIP Tube")
      (fields (field (name "MANUFACTURER") "Recom"))
      (libsource (lib "CAN_Optical_SchLib") (part "ROE-0505S"))
    )
    (comp (ref "U4")
      (value "1-406541-1")
      (footprint "1-406541-1")
      (fields (field (name "DIGI-KEY PART NUMBER") "A97716-ND"))
      (libsource (lib "CAN_Optical_SchLib") (part "1-406541-1"))
    )
    (comp (ref "U5")
      (value "1-406541-1")
      (footprint "1-406541-1")
      (fields (field (name "DIGI-KEY PART NUMBER") "A97716-ND"))
      (libsource (lib "CAN_Optical_SchLib") (part "1-406541-1"))
    )
    (comp (ref "U6")
      (value "1-406541-1")
      (footprint "1-406541-1")
      (fields (field (name "DIGI-KEY PART NUMBER") "A97716-ND"))
      (libsource (lib "CAN_Optical_SchLib") (part "1-406541-1"))
    )
    (comp (ref "USB1")
      (value "1734035-3")
      (footprint "USB-1734035")
      (description "CONN MINI B USB R/A SMD")
      (fields (field (name "MANUFACTURER") "TE Connectivity"))
      (libsource (lib "CAN_Optical_SchLib") (part "1734035-3"))
    )
  )
  (nets
    (net (code "1") (name "+3V3") (class "Default")
      (node (ref "C20") (pin "1") (pinfunction "1_1") (pintype "passive"))
      (node (ref "C27") (pin "1") (pinfunction "1_1") (pintype "passive"))
      (node (ref "C28") (pin "1") (pinfunction "1_1") (pintype "passive"))
      (node (ref "C30") (pin "1") (pinfunction "1_1") (pintype "passive"))
      (node (ref "C38") (pin "1") (pinfunction "1_1") (pintype "passive"))
      (node (ref "C6") (pin "1") (pinfunction "1_1") (pintype "passive"))
      (node (ref "C7") (pin "1") (pinfunction "1_1") (pintype "passive"))
      (node (ref "C9") (pin "1") (pinfunction "1_1") (pintype "passive"))
      (node (ref "D1") (pin "2") (pinfunction "2_2") (pintype "passive"))
      (node (ref "IC1") (pin "16") (pinfunction "VDD_16") (pintype "power_in"))
      (node (ref "IC2") (pin "16") (pinfunction "VDD_16") (pintype "power_in"))
      (node (ref "IC3") (pin "16") (pinfunction "VDD_16") (pintype "power_in"))
      (node (ref "R1") (pin "1") (pinfunction "1_1") (pintype "passive"))
      (node (ref "R8") (pin "1") (pinfunction "1_1") (pintype "passive"))
      (node (ref "TR1") (pin "1") (pinfunction "VCC1_1") (pintype "passive"))
      (node (ref "TR2") (pin "1") (pinfunction "VCC1_1") (pintype "passive"))
      (node (ref "TR3") (pin "1") (pinfunction "VCC1_1") (pintype "passive"))
      (node (ref "TR4") (pin "1") (pinfunction "VCC1_1") (pintype "passive"))
      (node (ref "U1") (pin "2") (pinfunction "VOUT_2") (pintype "passive"))
    )
    (net (code "2") (name "+5V") (class "Default")
      (node (ref "C10") (pin "1") (pinfunction "1_1") (pintype "passive"))
      (node (ref "C11") (pin "1") (pinfunction "1_1") (pintype "passive"))
      (node (ref "C12") (pin "1") (pinfunction "1_1") (pintype "passive"))
      (node (ref "C13") (pin "1") (pinfunction "1_1") (pintype "passive"))
      (node (ref "C14") (pin "1") (pinfunction "1_1") (pintype "passive"))
      (node (ref "C16") (pin "1") (pinfunction "1_1") (pintype "passive"))
      (node (ref "C17") (pin "1") (pinfunction "1_1") (pintype "passive"))
      (node (ref "C19") (pin "1") (pinfunction "1_1") (pintype "passive"))
      (node (ref "C2") (pin "1") (pinfunction "1_1") (pintype "passive"))
      (node (ref "C21") (pin "1") (pinfunction "1_1") (pintype "passive"))
      (node (ref "C22") (pin "1") (pinfunction "1_1") (pintype "passive"))
      (node (ref "C23") (pin "1") (pinfunction "1_1") (pintype "passive"))
      (node (ref "C24") (pin "1") (pinfunction "1_1") (pintype "passive"))
      (node (ref "C26") (pin "1") (pinfunction "1_1") (pintype "passive"))
      (node (ref "C31") (pin "1") (pinfunction "1_1") (pintype "passive"))
      (node (ref "C32") (pin "1") (pinfunction "1_1") (pintype "passive"))
      (node (ref "C33") (pin "1") (pinfunction "1_1") (pintype "passive"))
      (node (ref "C34") (pin "1") (pinfunction "1_1") (pintype "passive"))
      (node (ref "C35") (pin "1") (pinfunction "1_1") (pintype "passive"))
      (node (ref "C36") (pin "1") (pinfunction "1_1") (pintype "passive"))
      (node (ref "C37") (pin "1") (pinfunction "1_1") (pintype "passive"))
      (node (ref "C39") (pin "1") (pinfunction "1_1") (pintype "passive"))
      (node (ref "C40") (pin "1") (pinfunction "1_1") (pintype "passive"))
      (node (ref "C41") (pin "1") (pinfunction "1_1") (pintype "passive"))
      (node (ref "C42") (pin "1") (pinfunction "1_1") (pintype "passive"))
      (node (ref "C43") (pin "1") (pinfunction "1_1") (pintype "passive"))
      (node (ref "C44") (pin "1") (pinfunction "1_1") (pintype "passive"))
      (node (ref "C45") (pin "1") (pinfunction "1_1") (pintype "passive"))
      (node (ref "C46") (pin "1") (pinfunction "1_1") (pintype "passive"))
      (node (ref "C47") (pin "1") (pinfunction "1_1") (pintype "passive"))
      (node (ref "C48") (pin "1") (pinfunction "1_1") (pintype "passive"))
      (node (ref "C49") (pin "1") (pinfunction "1_1") (pintype "passive"))
      (node (ref "C50") (pin "1") (pinfunction "1_1") (pintype "passive"))
      (node (ref "C51") (pin "1") (pinfunction "1_1") (pintype "passive"))
      (node (ref "Dr1") (pin "1") (pinfunction "1A_1") (pintype "passive"))
      (node (ref "Dr1") (pin "6") (pinfunction "2A_6") (pintype "passive"))
      (node (ref "Dr1") (pin "8") (pinfunction "VCC_8") (pintype "passive"))
      (node (ref "Dr2") (pin "1") (pinfunction "1A_1") (pintype "passive"))
      (node (ref "Dr2") (pin "6") (pinfunction "2A_6") (pintype "passive"))
      (node (ref "Dr2") (pin "8") (pinfunction "VCC_8") (pintype "passive"))
      (node (ref "Dr3") (pin "1") (pinfunction "1A_1") (pintype "passive"))
      (node (ref "Dr3") (pin "8") (pinfunction "VCC_8") (pintype "passive"))
      (node (ref "Dr4") (pin "1") (pinfunction "1A_1") (pintype "passive"))
      (node (ref "Dr4") (pin "6") (pinfunction "2A_6") (pintype "passive"))
      (node (ref "Dr4") (pin "8") (pinfunction "VCC_8") (pintype "passive"))
      (node (ref "Dr5") (pin "1") (pinfunction "1A_1") (pintype "passive"))
      (node (ref "Dr5") (pin "6") (pinfunction "2A_6") (pintype "passive"))
      (node (ref "Dr5") (pin "8") (pinfunction "VCC_8") (pintype "passive"))
      (node (ref "IC1") (pin "1") (pinfunction "VCC_1") (pintype "power_in"))
      (node (ref "IC1") (pin "15") (pinfunction "ENABLED_15") (pintype "passive"))
      (node (ref "IC1") (pin "2") (pinfunction "ENABLEA_2") (pintype "passive"))
      (node (ref "IC1") (pin "7") (pinfunction "ENABLEB_7") (pintype "passive"))
      (node (ref "IC1") (pin "9") (pinfunction "ENABLEC_9") (pintype "passive"))
      (node (ref "IC2") (pin "1") (pinfunction "VCC_1") (pintype "power_in"))
      (node (ref "IC2") (pin "2") (pinfunction "ENABLEA_2") (pintype "passive"))
      (node (ref "IC3") (pin "1") (pinfunction "VCC_1") (pintype "power_in"))
      (node (ref "IC3") (pin "15") (pinfunction "ENABLED_15") (pintype "passive"))
      (node (ref "IC3") (pin "2") (pinfunction "ENABLEA_2") (pintype "passive"))
      (node (ref "IC3") (pin "7") (pinfunction "ENABLEB_7") (pintype "passive"))
      (node (ref "IC3") (pin "9") (pinfunction "ENABLEC_9") (pintype "passive"))
      (node (ref "J1") (pin "112") (pinfunction "5V0_112") (pintype "passive"))
      (node (ref "J1") (pin "158") (pinfunction "5V0_158") (pintype "passive"))
      (node (ref "J1") (pin "180") (pinfunction "5V0_180") (pintype "passive"))
      (node (ref "J1") (pin "48") (pinfunction "5V0_48") (pintype "passive"))
      (node (ref "J1") (pin "84") (pinfunction "5V0_84") (pintype "passive"))
      (node (ref "J1") (pin "98") (pinfunction "5V0_98") (pintype "passive"))
      (node (ref "L1") (pin "1") (pinfunction "1_1") (pintype "passive"))
      (node (ref "R10") (pin "1") (pinfunction "1_1") (pintype "passive"))
      (node (ref "R11") (pin "1") (pinfunction "1_1") (pintype "passive"))
      (node (ref "R12") (pin "1") (pinfunction "1_1") (pintype "passive"))
      (node (ref "R13") (pin "1") (pinfunction "1_1") (pintype "passive"))
      (node (ref "R14") (pin "1") (pinfunction "1_1") (pintype "passive"))
      (node (ref "R4") (pin "1") (pinfunction "1_1") (pintype "passive"))
      (node (ref "R5") (pin "1") (pinfunction "1_1") (pintype "passive"))
      (node (ref "R6") (pin "1") (pinfunction "1_1") (pintype "passive"))
      (node (ref "R7") (pin "1") (pinfunction "1_1") (pintype "passive"))
      (node (ref "Rx1") (pin "3") (pinfunction "3_3") (pintype "passive"))
      (node (ref "Rx2") (pin "3") (pinfunction "3_3") (pintype "passive"))
      (node (ref "Rx3") (pin "3") (pinfunction "3_3") (pintype "passive"))
      (node (ref "Rx4") (pin "3") (pinfunction "3_3") (pintype "passive"))
      (node (ref "Rx5") (pin "3") (pinfunction "3_3") (pintype "passive"))
      (node (ref "Rx6") (pin "3") (pinfunction "3_3") (pintype "passive"))
      (node (ref "Rx7") (pin "3") (pinfunction "3_3") (pintype "passive"))
      (node (ref "Rx8") (pin "3") (pinfunction "3_3") (pintype "passive"))
      (node (ref "Rx9") (pin "3") (pinfunction "3_3") (pintype "passive"))
      (node (ref "U1") (pin "7") (pinfunction "EN_7") (pintype "passive"))
      (node (ref "U1") (pin "8") (pinfunction "VIN_8") (pintype "passive"))
      (node (ref "sw1") (pin "2") (pinfunction "2_2") (pintype "passive"))
    )
    (net (code "3") (name "+5V{slash}1") (class "Default")
      (node (ref "C1") (pin "1") (pinfunction "1_1") (pintype "passive"))
      (node (ref "C18") (pin "1") (pinfunction "1_1") (pintype "passive"))
      (node (ref "C25") (pin "1") (pinfunction "1_1") (pintype "passive"))
      (node (ref "C29") (pin "1") (pinfunction "1_1") (pintype "passive"))
      (node (ref "C3") (pin "1") (pinfunction "1_1") (pintype "passive"))
      (node (ref "TR1") (pin "8") (pinfunction "VCC2_8") (pintype "passive"))
      (node (ref "TR2") (pin "8") (pinfunction "VCC2_8") (pintype "passive"))
      (node (ref "TR3") (pin "8") (pinfunction "VCC2_8") (pintype "passive"))
      (node (ref "TR4") (pin "8") (pinfunction "VCC2_8") (pintype "passive"))
      (node (ref "U3") (pin "4") (pinfunction "+Vout_4") (pintype "passive"))
    )
    (net (code "4") (name "/DACA") (class "Default")
      (node (ref "J1") (pin "9") (pinfunction "ADC/DACA_9") (pintype "passive"))
      (node (ref "tp17") (pin "1") (pinfunction "1_1") (pintype "passive"))
    )
    (net (code "5") (name "/DACB") (class "Default")
      (node (ref "J1") (pin "11") (pinfunction "ADC/DACB_11") (pintype "passive"))
      (node (ref "tp18") (pin "1") (pinfunction "1_1") (pintype "passive"))
    )
    (net (code "6") (name "/RXA") (class "Default")
      (node (ref "IC1") (pin "4") (pinfunction "E_4") (pintype "passive"))
      (node (ref "J1") (pin "80") (pinfunction "CANRXA_80") (pintype "passive"))
      (node (ref "TR1") (pin "2") (pinfunction "RX_2") (pintype "passive"))
      (node (ref "tp1") (pin "1") (pinfunction "1_1") (pintype "passive"))
    )
    (net (code "7") (name "/RXA5V") (class "Default")
      (node (ref "IC1") (pin "3") (pinfunction "A_3") (pintype "passive"))
      (node (ref "Rx1") (pin "1") (pinfunction "Signal_1") (pintype "passive"))
      (node (ref "Rx1") (pin "4") (pinfunction "VCC_4") (pintype "passive"))
    )
    (net (code "8") (name "/RXB") (class "Default")
      (node (ref "IC1") (pin "11") (pinfunction "G_11") (pintype "passive"))
      (node (ref "J1") (pin "70") (pinfunction "QEP1-B_70") (pintype "passive"))
      (node (ref "TR3") (pin "2") (pinfunction "RX_2") (pintype "passive"))
      (node (ref "tp6") (pin "1") (pinfunction "1_1") (pintype "passive"))
    )
    (net (code "9") (name "/RXB5V") (class "Default")
      (node (ref "IC1") (pin "10") (pinfunction "C_10") (pintype "passive"))
      (node (ref "Rx3") (pin "1") (pinfunction "Signal_1") (pintype "passive"))
      (node (ref "Rx3") (pin "4") (pinfunction "VCC_4") (pintype "passive"))
    )
    (net (code "10") (name "/SHRXA") (class "Default")
      (node (ref "Dr2") (pin "2") (pinfunction "1B_2") (pintype "passive"))
      (node (ref "TR2") (pin "2") (pinfunction "RX_2") (pintype "passive"))
      (node (ref "tp2") (pin "1") (pinfunction "1_1") (pintype "passive"))
    )
    (net (code "11") (name "/SHRXB") (class "Default")
      (node (ref "Dr2") (pin "7") (pinfunction "2B_7") (pintype "passive"))
      (node (ref "TR4") (pin "2") (pinfunction "RX_2") (pintype "passive"))
      (node (ref "tp7") (pin "1") (pinfunction "1_1") (pintype "passive"))
    )
    (net (code "12") (name "/SHTXA") (class "Default")
      (node (ref "IC1") (pin "5") (pinfunction "F_5") (pintype "passive"))
      (node (ref "TR2") (pin "3") (pinfunction "TX_3") (pintype "passive"))
      (node (ref "tp4") (pin "1") (pinfunction "1_1") (pintype "passive"))
    )
    (net (code "13") (name "/SHTXA5V") (class "Default")
      (node (ref "IC1") (pin "6") (pinfunction "B_6") (pintype "passive"))
      (node (ref "Rx2") (pin "1") (pinfunction "Signal_1") (pintype "passive"))
      (node (ref "Rx2") (pin "4") (pinfunction "VCC_4") (pintype "passive"))
    )
    (net (code "14") (name "/SHTXB") (class "Default")
      (node (ref "IC1") (pin "13") (pinfunction "H_13") (pintype "passive"))
      (node (ref "TR4") (pin "3") (pinfunction "TX_3") (pintype "passive"))
      (node (ref "tp9") (pin "1") (pinfunction "1_1") (pintype "passive"))
    )
    (net (code "15") (name "/SHTXB5V") (class "Default")
      (node (ref "IC1") (pin "14") (pinfunction "D_14") (pintype "passive"))
      (node (ref "Rx4") (pin "1") (pinfunction "Signal_1") (pintype "passive"))
      (node (ref "Rx4") (pin "4") (pinfunction "VCC_4") (pintype "passive"))
    )
    (net (code "16") (name "/SPICLKA") (class "Default")
      (node (ref "Dr5") (pin "2") (pinfunction "1B_2") (pintype "passive"))
      (node (ref "IC3") (pin "11") (pinfunction "G_11") (pintype "passive"))
      (node (ref "J1") (pin "71") (pinfunction "SPICLKA_71") (pintype "passive"))
      (node (ref "sma13") (pin "1") (pinfunction "signal_1") (pintype "passive"))
      (node (ref "tp15") (pin "1") (pinfunction "1_1") (pintype "passive"))
    )
    (net (code "17") (name "/SPICLKA5V") (class "Default")
      (node (ref "IC3") (pin "10") (pinfunction "C_10") (pintype "passive"))
      (node (ref "Rx8") (pin "1") (pinfunction "Signal_1") (pintype "passive"))
      (node (ref "Rx8") (pin "4") (pinfunction "VCC_4") (pintype "passive"))
    )
    (net (code "18") (name "/SPISIMOA") (class "Default")
      (node (ref "Dr4") (pin "2") (pinfunction "1B_2") (pintype "passive"))
      (node (ref "IC3") (pin "4") (pinfunction "E_4") (pintype "passive"))
      (node (ref "J1") (pin "67") (pinfunction "SPISIMOA_67") (pintype "passive"))
      (node (ref "sma11") (pin "1") (pinfunction "signal_1") (pintype "passive"))
      (node (ref "tp13") (pin "1") (pinfunction "1_1") (pintype "passive"))
    )
    (net (code "19") (name "/SPISIMOA5V") (class "Default")
      (node (ref "IC3") (pin "3") (pinfunction "A_3") (pintype "passive"))
      (node (ref "Rx6") (pin "1") (pinfunction "Signal_1") (pintype "passive"))
      (node (ref "Rx6") (pin "4") (pinfunction "VCC_4") (pintype "passive"))
    )
    (net (code "20") (name "/SPISOMIA") (class "Default")
      (node (ref "Dr4") (pin "7") (pinfunction "2B_7") (pintype "passive"))
      (node (ref "IC3") (pin "5") (pinfunction "F_5") (pintype "passive"))
      (node (ref "J1") (pin "69") (pinfunction "SPISOMIA_69") (pintype "passive"))
      (node (ref "sma12") (pin "1") (pinfunction "signal_1") (pintype "passive"))
      (node (ref "tp14") (pin "1") (pinfunction "1_1") (pintype "passive"))
    )
    (net (code "21") (name "/SPISOMIA5V") (class "Default")
      (node (ref "IC3") (pin "6") (pinfunction "B_6") (pintype "passive"))
      (node (ref "Rx7") (pin "1") (pinfunction "Signal_1") (pintype "passive"))
      (node (ref "Rx7") (pin "4") (pinfunction "VCC_4") (pintype "passive"))
    )
    (net (code "22") (name "/SPISTEA") (class "Default")
      (node (ref "Dr5") (pin "7") (pinfunction "2B_7") (pintype "passive"))
      (node (ref "IC3") (pin "13") (pinfunction "H_13") (pintype "passive"))
      (node (ref "J1") (pin "73") (pinfunction "SPISTEA_73") (pintype "passive"))
      (node (ref "sma14") (pin "1") (pinfunction "signal_1") (pintype "passive"))
      (node (ref "tp16") (pin "1") (pinfunction "1_1") (pintype "passive"))
    )
    (net (code "23") (name "/SPISTEA5V") (class "Default")
      (node (ref "IC3") (pin "14") (pinfunction "D_14") (pintype "passive"))
      (node (ref "Rx9") (pin "1") (pinfunction "Signal_1") (pintype "passive"))
      (node (ref "Rx9") (pin "4") (pinfunction "VCC_4") (pintype "passive"))
    )
    (net (code "24") (name "/TXA") (class "Default")
      (node (ref "Dr1") (pin "2") (pinfunction "1B_2") (pintype "passive"))
      (node (ref "J1") (pin "82") (pinfunction "CANTXA_82") (pintype "passive"))
      (node (ref "R1") (pin "2") (pinfunction "2_2") (pintype "passive"))
      (node (ref "TR1") (pin "3") (pinfunction "TX_3") (pintype "passive"))
      (node (ref "tp3") (pin "1") (pinfunction "1_1") (pintype "passive"))
    )
    (net (code "25") (name "/TXB") (class "Default")
      (node (ref "Dr1") (pin "7") (pinfunction "2B_7") (pintype "passive"))
      (node (ref "J1") (pin "68") (pinfunction "QEP1-A_68") (pintype "passive"))
      (node (ref "R8") (pin "2") (pinfunction "2_2") (pintype "passive"))
      (node (ref "TR3") (pin "3") (pinfunction "TX_3") (pintype "passive"))
      (node (ref "tp8") (pin "1") (pinfunction "1_1") (pintype "passive"))
    )
    (net (code "26") (name "/UARTRXA") (class "Default")
      (node (ref "IC2") (pin "4") (pinfunction "E_4") (pintype "passive"))
      (node (ref "J1") (pin "76") (pinfunction "SCIRXA_76") (pintype "passive"))
      (node (ref "sma10") (pin "1") (pinfunction "signal_1") (pintype "passive"))
      (node (ref "sma16") (pin "1") (pinfunction "signal_1") (pintype "passive"))
      (node (ref "tp12") (pin "1") (pinfunction "1_1") (pintype "passive"))
    )
    (net (code "27") (name "/UARTRXA5V") (class "Default")
      (node (ref "IC2") (pin "3") (pinfunction "A_3") (pintype "passive"))
      (node (ref "Rx5") (pin "1") (pinfunction "Signal_1") (pintype "passive"))
      (node (ref "Rx5") (pin "4") (pinfunction "VCC_4") (pintype "passive"))
    )
    (net (code "28") (name "/UARTTXA") (class "Default")
      (node (ref "Dr3") (pin "2") (pinfunction "1B_2") (pintype "passive"))
      (node (ref "J1") (pin "78") (pinfunction "SCITXA_78") (pintype "passive"))
      (node (ref "sma15") (pin "1") (pinfunction "signal_1") (pintype "passive"))
      (node (ref "sma9") (pin "1") (pinfunction "signal_1") (pintype "passive"))
      (node (ref "tp11") (pin "1") (pinfunction "1_1") (pintype "passive"))
    )
    (net (code "29") (name "GND") (class "Default")
      (node (ref "C10") (pin "2") (pinfunction "2_2") (pintype "passive"))
      (node (ref "C11") (pin "2") (pinfunction "2_2") (pintype "passive"))
      (node (ref "C12") (pin "2") (pinfunction "2_2") (pintype "passive"))
      (node (ref "C13") (pin "2") (pinfunction "2_2") (pintype "passive"))
      (node (ref "C14") (pin "2") (pinfunction "2_2") (pintype "passive"))
      (node (ref "C15") (pin "2") (pinfunction "2_2") (pintype "passive"))
      (node (ref "C16") (pin "2") (pinfunction "2_2") (pintype "passive"))
      (node (ref "C17") (pin "2") (pinfunction "2_2") (pintype "passive"))
      (node (ref "C19") (pin "2") (pinfunction "2_2") (pintype "passive"))
      (node (ref "C2") (pin "2") (pinfunction "2_2") (pintype "passive"))
      (node (ref "C20") (pin "2") (pinfunction "2_2") (pintype "passive"))
      (node (ref "C21") (pin "2") (pinfunction "2_2") (pintype "passive"))
      (node (ref "C22") (pin "2") (pinfunction "2_2") (pintype "passive"))
      (node (ref "C23") (pin "2") (pinfunction "2_2") (pintype "passive"))
      (node (ref "C24") (pin "2") (pinfunction "2_2") (pintype "passive"))
      (node (ref "C26") (pin "2") (pinfunction "2_2") (pintype "passive"))
      (node (ref "C27") (pin "2") (pinfunction "2_2") (pintype "passive"))
      (node (ref "C28") (pin "2") (pinfunction "2_2") (pintype "passive"))
      (node (ref "C30") (pin "2") (pinfunction "2_2") (pintype "passive"))
      (node (ref "C31") (pin "2") (pinfunction "2_2") (pintype "passive"))
      (node (ref "C32") (pin "2") (pinfunction "2_2") (pintype "passive"))
      (node (ref "C33") (pin "2") (pinfunction "2_2") (pintype "passive"))
      (node (ref "C34") (pin "2") (pinfunction "2_2") (pintype "passive"))
      (node (ref "C35") (pin "2") (pinfunction "2_2") (pintype "passive"))
      (node (ref "C36") (pin "2") (pinfunction "2_2") (pintype "passive"))
      (node (ref "C37") (pin "2") (pinfunction "2_2") (pintype "passive"))
      (node (ref "C38") (pin "2") (pinfunction "2_2") (pintype "passive"))
      (node (ref "C39") (pin "2") (pinfunction "2_2") (pintype "passive"))
      (node (ref "C4") (pin "2") (pinfunction "2_2") (pintype "passive"))
      (node (ref "C40") (pin "2") (pinfunction "2_2") (pintype "passive"))
      (node (ref "C41") (pin "2") (pinfunction "2_2") (pintype "passive"))
      (node (ref "C42") (pin "2") (pinfunction "2_2") (pintype "passive"))
      (node (ref "C43") (pin "2") (pinfunction "2_2") (pintype "passive"))
      (node (ref "C44") (pin "2") (pinfunction "2_2") (pintype "passive"))
      (node (ref "C45") (pin "2") (pinfunction "2_2") (pintype "passive"))
      (node (ref "C46") (pin "2") (pinfunction "2_2") (pintype "passive"))
      (node (ref "C47") (pin "2") (pinfunction "2_2") (pintype "passive"))
      (node (ref "C48") (pin "2") (pinfunction "2_2") (pintype "passive"))
      (node (ref "C49") (pin "2") (pinfunction "2_2") (pintype "passive"))
      (node (ref "C5") (pin "2") (pinfunction "2_2") (pintype "passive"))
      (node (ref "C50") (pin "2") (pinfunction "2_2") (pintype "passive"))
      (node (ref "C51") (pin "2") (pinfunction "2_2") (pintype "passive"))
      (node (ref "C6") (pin "2") (pinfunction "2_2") (pintype "passive"))
      (node (ref "C7") (pin "2") (pinfunction "2_2") (pintype "passive"))
      (node (ref "C8") (pin "2") (pinfunction "2_2") (pintype "passive"))
      (node (ref "C9") (pin "2") (pinfunction "2_2") (pintype "passive"))
      (node (ref "CON1") (pin "2") (pinfunction "2_2") (pintype "passive"))
      (node (ref "Dr1") (pin "4") (pinfunction "GND_4") (pintype "passive"))
      (node (ref "Dr2") (pin "4") (pinfunction "GND_4") (pintype "passive"))
      (node (ref "Dr3") (pin "4") (pinfunction "GND_4") (pintype "passive"))
      (node (ref "Dr4") (pin "4") (pinfunction "GND_4") (pintype "passive"))
      (node (ref "Dr5") (pin "4") (pinfunction "GND_4") (pintype "passive"))
      (node (ref "IC1") (pin "8") (pinfunction "VSS_8") (pintype "power_in"))
      (node (ref "IC2") (pin "8") (pinfunction "VSS_8") (pintype "power_in"))
      (node (ref "IC3") (pin "8") (pinfunction "VSS_8") (pintype "power_in"))
      (node (ref "J1") (pin "10") (pinfunction "GND_10") (pintype "passive"))
      (node (ref "J1") (pin "111") (pinfunction "GND_111") (pintype "passive"))
      (node (ref "J1") (pin "135") (pinfunction "GND_135") (pintype "passive"))
      (node (ref "J1") (pin "157") (pinfunction "GND_157") (pintype "passive"))
      (node (ref "J1") (pin "179") (pinfunction "GND_179") (pintype "passive"))
      (node (ref "J1") (pin "19") (pinfunction "GND_19") (pintype "passive"))
      (node (ref "J1") (pin "22") (pinfunction "GND_22") (pintype "passive"))
      (node (ref "J1") (pin "35") (pinfunction "GND_35") (pintype "passive"))
      (node (ref "J1") (pin "38") (pinfunction "GND_38") (pintype "passive"))
      (node (ref "J1") (pin "46") (pinfunction "GND_46") (pintype "passive"))
      (node (ref "J1") (pin "47") (pinfunction "GND_47") (pintype "passive"))
      (node (ref "J1") (pin "65") (pinfunction "GND_65") (pintype "passive"))
      (node (ref "J1") (pin "7") (pinfunction "GND_7") (pintype "passive"))
      (node (ref "J1") (pin "83") (pinfunction "GND_83") (pintype "passive"))
      (node (ref "J1") (pin "97") (pinfunction "GND_97") (pintype "passive"))
      (node (ref "R2") (pin "1") (pinfunction "1_1") (pintype "passive"))
      (node (ref "Rx1") (pin "2") (pintype "passive"))
      (node (ref "Rx2") (pin "2") (pintype "passive"))
      (node (ref "Rx3") (pin "2") (pintype "passive"))
      (node (ref "Rx4") (pin "2") (pintype "passive"))
      (node (ref "Rx5") (pin "2") (pintype "passive"))
      (node (ref "Rx6") (pin "2") (pintype "passive"))
      (node (ref "Rx7") (pin "2") (pintype "passive"))
      (node (ref "Rx8") (pin "2") (pintype "passive"))
      (node (ref "Rx9") (pin "2") (pintype "passive"))
      (node (ref "TR1") (pin "4") (pinfunction "GND1_4") (pintype "passive"))
      (node (ref "TR2") (pin "4") (pinfunction "GND1_4") (pintype "passive"))
      (node (ref "TR3") (pin "4") (pinfunction "GND1_4") (pintype "passive"))
      (node (ref "TR4") (pin "4") (pinfunction "GND1_4") (pintype "passive"))
      (node (ref "Tx1") (pin "2") (pinfunction "Cathode_2") (pintype "passive"))
      (node (ref "Tx2") (pin "2") (pinfunction "Cathode_2") (pintype "passive"))
      (node (ref "Tx3") (pin "2") (pinfunction "Cathode_2") (pintype "passive"))
      (node (ref "Tx4") (pin "2") (pinfunction "Cathode_2") (pintype "passive"))
      (node (ref "Tx5") (pin "2") (pinfunction "Cathode_2") (pintype "passive"))
      (node (ref "Tx6") (pin "2") (pinfunction "Cathode_2") (pintype "passive"))
      (node (ref "Tx7") (pin "2") (pinfunction "Cathode_2") (pintype "passive"))
      (node (ref "Tx8") (pin "2") (pinfunction "Cathode_2") (pintype "passive"))
      (node (ref "Tx9") (pin "2") (pinfunction "Cathode_2") (pintype "passive"))
      (node (ref "U1") (pin "4") (pinfunction "GND_4") (pintype "passive"))
      (node (ref "U3") (pin "1") (pinfunction "-Vin_1") (pintype "passive"))
      (node (ref "USB1") (pin "5") (pinfunction "GND_5") (pintype "passive"))
      (node (ref "sma10") (pin "2") (pinfunction "gnd_2") (pintype "passive"))
      (node (ref "sma11") (pin "2") (pinfunction "gnd_2") (pintype "passive"))
      (node (ref "sma12") (pin "2") (pinfunction "gnd_2") (pintype "passive"))
      (node (ref "sma13") (pin "2") (pinfunction "gnd_2") (pintype "passive"))
      (node (ref "sma14") (pin "2") (pinfunction "gnd_2") (pintype "passive"))
      (node (ref "sma15") (pin "2") (pinfunction "gnd_2") (pintype "passive"))
      (node (ref "sma16") (pin "2") (pinfunction "gnd_2") (pintype "passive"))
      (node (ref "sma9") (pin "2") (pinfunction "gnd_2") (pintype "passive"))
      (node (ref "tp1") (pin "2") (pinfunction "2_2") (pintype "passive"))
      (node (ref "tp11") (pin "2") (pinfunction "2_2") (pintype "passive"))
      (node (ref "tp12") (pin "2") (pinfunction "2_2") (pintype "passive"))
      (node (ref "tp13") (pin "2") (pinfunction "2_2") (pintype "passive"))
      (node (ref "tp14") (pin "2") (pinfunction "2_2") (pintype "passive"))
      (node (ref "tp15") (pin "2") (pinfunction "2_2") (pintype "passive"))
      (node (ref "tp16") (pin "2") (pinfunction "2_2") (pintype "passive"))
      (node (ref "tp17") (pin "2") (pinfunction "2_2") (pintype "passive"))
      (node (ref "tp18") (pin "2") (pinfunction "2_2") (pintype "passive"))
      (node (ref "tp2") (pin "2") (pinfunction "2_2") (pintype "passive"))
      (node (ref "tp3") (pin "2") (pinfunction "2_2") (pintype "passive"))
      (node (ref "tp4") (pin "2") (pinfunction "2_2") (pintype "passive"))
      (node (ref "tp6") (pin "2") (pinfunction "2_2") (pintype "passive"))
      (node (ref "tp7") (pin "2") (pinfunction "2_2") (pintype "passive"))
      (node (ref "tp8") (pin "2") (pinfunction "2_2") (pintype "passive"))
      (node (ref "tp9") (pin "2") (pinfunction "2_2") (pintype "passive"))
    )
    (net (code "30") (name "GND{slash}1") (class "Default")
      (node (ref "C1") (pin "2") (pinfunction "2_2") (pintype "passive"))
      (node (ref "C18") (pin "2") (pinfunction "2_2") (pintype "passive"))
      (node (ref "C25") (pin "2") (pinfunction "2_2") (pintype "passive"))
      (node (ref "C29") (pin "2") (pinfunction "2_2") (pintype "passive"))
      (node (ref "C3") (pin "2") (pinfunction "2_2") (pintype "passive"))
      (node (ref "TR1") (pin "5") (pinfunction "GND2_5") (pintype "passive"))
      (node (ref "TR2") (pin "5") (pinfunction "GND2_5") (pintype "passive"))
      (node (ref "TR3") (pin "5") (pinfunction "GND2_5") (pintype "passive"))
      (node (ref "TR4") (pin "5") (pinfunction "GND2_5") (pintype "passive"))
      (node (ref "U2") (pin "4") (pinfunction "4_4") (pintype "passive"))
      (node (ref "U2") (pin "5") (pinfunction "5_5") (pintype "passive"))
      (node (ref "U2") (pin "9") (pinfunction "9_9") (pintype "passive"))
      (node (ref "U3") (pin "3") (pinfunction "-Vout_3") (pintype "passive"))
      (node (ref "U4") (pin "4") (pinfunction "4_4") (pintype "passive"))
      (node (ref "U4") (pin "5") (pinfunction "5_5") (pintype "passive"))
      (node (ref "U4") (pin "9") (pinfunction "9_9") (pintype "passive"))
      (node (ref "U5") (pin "4") (pinfunction "4_4") (pintype "passive"))
      (node (ref "U5") (pin "5") (pinfunction "5_5") (pintype "passive"))
      (node (ref "U5") (pin "9") (pinfunction "9_9") (pintype "passive"))
      (node (ref "U6") (pin "4") (pinfunction "4_4") (pintype "passive"))
      (node (ref "U6") (pin "5") (pinfunction "5_5") (pintype "passive"))
      (node (ref "U6") (pin "9") (pinfunction "9_9") (pintype "passive"))
    )
    (net (code "31") (name "Net-(D1-Pad1)") (class "Default")
      (node (ref "D1") (pin "1") (pinfunction "1_1") (pintype "passive"))
      (node (ref "R2") (pin "2") (pinfunction "2_2") (pintype "passive"))
    )
    (net (code "32") (name "Net-(Dr1-1Y)") (class "Default")
      (node (ref "Dr1") (pin "3") (pinfunction "1Y_3") (pintype "passive"))
      (node (ref "R4") (pin "2") (pinfunction "2_2") (pintype "passive"))
      (node (ref "Tx1") (pin "1") (pinfunction "Anode_1") (pintype "passive"))
    )
    (net (code "33") (name "Net-(Dr1-2Y)") (class "Default")
      (node (ref "Dr1") (pin "5") (pinfunction "2Y_5") (pintype "passive"))
      (node (ref "R6") (pin "2") (pinfunction "2_2") (pintype "passive"))
      (node (ref "Tx3") (pin "1") (pinfunction "Anode_1") (pintype "passive"))
    )
    (net (code "34") (name "Net-(Dr2-1Y)") (class "Default")
      (node (ref "Dr2") (pin "3") (pinfunction "1Y_3") (pintype "passive"))
      (node (ref "R5") (pin "2") (pinfunction "2_2") (pintype "passive"))
      (node (ref "Tx2") (pin "1") (pinfunction "Anode_1") (pintype "passive"))
    )
    (net (code "35") (name "Net-(Dr2-2Y)") (class "Default")
      (node (ref "Dr2") (pin "5") (pinfunction "2Y_5") (pintype "passive"))
      (node (ref "R7") (pin "2") (pinfunction "2_2") (pintype "passive"))
      (node (ref "Tx4") (pin "1") (pinfunction "Anode_1") (pintype "passive"))
    )
    (net (code "36") (name "Net-(Dr3-1Y)") (class "Default")
      (node (ref "Dr3") (pin "3") (pinfunction "1Y_3") (pintype "passive"))
      (node (ref "R10") (pin "2") (pinfunction "2_2") (pintype "passive"))
      (node (ref "Tx5") (pin "1") (pinfunction "Anode_1") (pintype "passive"))
    )
    (net (code "37") (name "Net-(Dr4-1Y)") (class "Default")
      (node (ref "Dr4") (pin "3") (pinfunction "1Y_3") (pintype "passive"))
      (node (ref "R11") (pin "2") (pinfunction "2_2") (pintype "passive"))
      (node (ref "Tx6") (pin "1") (pinfunction "Anode_1") (pintype "passive"))
    )
    (net (code "38") (name "Net-(Dr4-2Y)") (class "Default")
      (node (ref "Dr4") (pin "5") (pinfunction "2Y_5") (pintype "passive"))
      (node (ref "R13") (pin "2") (pinfunction "2_2") (pintype "passive"))
      (node (ref "Tx8") (pin "1") (pinfunction "Anode_1") (pintype "passive"))
    )
    (net (code "39") (name "Net-(Dr5-1Y)") (class "Default")
      (node (ref "Dr5") (pin "3") (pinfunction "1Y_3") (pintype "passive"))
      (node (ref "R12") (pin "2") (pinfunction "2_2") (pintype "passive"))
      (node (ref "Tx7") (pin "1") (pinfunction "Anode_1") (pintype "passive"))
    )
    (net (code "40") (name "Net-(Dr5-2Y)") (class "Default")
      (node (ref "Dr5") (pin "5") (pinfunction "2Y_5") (pintype "passive"))
      (node (ref "R14") (pin "2") (pinfunction "2_2") (pintype "passive"))
      (node (ref "Tx9") (pin "1") (pinfunction "Anode_1") (pintype "passive"))
    )
    (net (code "41") (name "Net-(R3-Pad2)") (class "Default")
      (node (ref "R3") (pin "2") (pinfunction "2_2") (pintype "passive"))
      (node (ref "tp5") (pin "2") (pinfunction "2_2") (pintype "passive"))
    )
    (net (code "42") (name "Net-(R9-Pad2)") (class "Default")
      (node (ref "R9") (pin "2") (pinfunction "2_2") (pintype "passive"))
      (node (ref "tp10") (pin "2") (pinfunction "2_2") (pintype "passive"))
    )
    (net (code "43") (name "Net-(TR1-CANH)") (class "Default")
      (node (ref "R3") (pin "1") (pinfunction "1_1") (pintype "passive"))
      (node (ref "TR1") (pin "7") (pinfunction "CANH_7") (pintype "passive"))
      (node (ref "TR2") (pin "7") (pinfunction "CANH_7") (pintype "passive"))
      (node (ref "U2") (pin "1") (pinfunction "1_1") (pintype "passive"))
      (node (ref "U5") (pin "1") (pinfunction "1_1") (pintype "passive"))
    )
    (net (code "44") (name "Net-(TR1-CANL)") (class "Default")
      (node (ref "TR1") (pin "6") (pinfunction "CANL_6") (pintype "passive"))
      (node (ref "TR2") (pin "6") (pinfunction "CANL_6") (pintype "passive"))
      (node (ref "U2") (pin "2") (pinfunction "2_2") (pintype "passive"))
      (node (ref "U5") (pin "2") (pinfunction "2_2") (pintype "passive"))
      (node (ref "tp5") (pin "1") (pinfunction "1_1") (pintype "passive"))
    )
    (net (code "45") (name "Net-(TR3-CANH)") (class "Default")
      (node (ref "R9") (pin "1") (pinfunction "1_1") (pintype "passive"))
      (node (ref "TR3") (pin "7") (pinfunction "CANH_7") (pintype "passive"))
      (node (ref "TR4") (pin "7") (pinfunction "CANH_7") (pintype "passive"))
      (node (ref "U4") (pin "1") (pinfunction "1_1") (pintype "passive"))
      (node (ref "U6") (pin "1") (pinfunction "1_1") (pintype "passive"))
    )
    (net (code "46") (name "Net-(TR3-CANL)") (class "Default")
      (node (ref "TR3") (pin "6") (pinfunction "CANL_6") (pintype "passive"))
      (node (ref "TR4") (pin "6") (pinfunction "CANL_6") (pintype "passive"))
      (node (ref "U4") (pin "2") (pinfunction "2_2") (pintype "passive"))
      (node (ref "U6") (pin "2") (pinfunction "2_2") (pintype "passive"))
      (node (ref "tp10") (pin "1") (pinfunction "1_1") (pintype "passive"))
    )
    (net (code "47") (name "Net-(U1-BYP)") (class "Default")
      (node (ref "C8") (pin "1") (pinfunction "1_1") (pintype "passive"))
      (node (ref "U1") (pin "3") (pinfunction "BYP_3") (pintype "passive"))
    )
    (net (code "48") (name "Net-(U1-REF)") (class "Default")
      (node (ref "C5") (pin "1") (pinfunction "1_1") (pintype "passive"))
      (node (ref "U1") (pin "5") (pinfunction "REF_SENSE_5") (pintype "passive"))
      (node (ref "U1") (pin "6") (pinfunction "REF_6") (pintype "passive"))
    )
    (net (code "49") (name "Net-(U1-VREG)") (class "Default")
      (node (ref "C4") (pin "1") (pinfunction "1_1") (pintype "passive"))
      (node (ref "U1") (pin "1") (pinfunction "VREG_1") (pintype "passive"))
    )
    (net (code "50") (name "Net-(U3-+Vin)") (class "Default")
      (node (ref "L1") (pin "2") (pinfunction "2_2") (pintype "passive"))
      (node (ref "U3") (pin "2") (pinfunction "+Vin_2") (pintype "passive"))
    )
    (net (code "51") (name "Net-(USB1-VCC)") (class "Default")
      (node (ref "C15") (pin "1") (pinfunction "1_1") (pintype "passive"))
      (node (ref "USB1") (pin "1") (pinfunction "VCC_1") (pintype "passive"))
      (node (ref "sw1") (pin "3") (pinfunction "3_3") (pintype "passive"))
    )
    (net (code "52") (name "VCC") (class "Default")
      (node (ref "CON1") (pin "1") (pinfunction "1_1") (pintype "passive"))
      (node (ref "sw1") (pin "1") (pinfunction "1_1") (pintype "passive"))
    )
    (net (code "53") (name "unconnected-(Dr3-2A-Pad6)") (class "Default")
      (node (ref "Dr3") (pin "6") (pinfunction "2A_6") (pintype "passive"))
    )
    (net (code "54") (name "unconnected-(Dr3-2B-Pad7)") (class "Default")
      (node (ref "Dr3") (pin "7") (pinfunction "2B_7") (pintype "passive"))
    )
    (net (code "55") (name "unconnected-(Dr3-2Y-Pad5)") (class "Default")
      (node (ref "Dr3") (pin "5") (pinfunction "2Y_5") (pintype "passive"))
    )
    (net (code "56") (name "unconnected-(IC1-NC-Pad12)") (class "Default")
      (node (ref "IC1") (pin "12") (pinfunction "NC_12") (pintype "passive"))
    )
    (net (code "57") (name "unconnected-(IC2-B-Pad6)") (class "Default")
      (node (ref "IC2") (pin "6") (pinfunction "B_6") (pintype "passive"))
    )
    (net (code "58") (name "unconnected-(IC2-C-Pad10)") (class "Default")
      (node (ref "IC2") (pin "10") (pinfunction "C_10") (pintype "passive"))
    )
    (net (code "59") (name "unconnected-(IC2-D-Pad14)") (class "Default")
      (node (ref "IC2") (pin "14") (pinfunction "D_14") (pintype "passive"))
    )
    (net (code "60") (name "unconnected-(IC2-ENABLEB-Pad7)") (class "Default")
      (node (ref "IC2") (pin "7") (pinfunction "ENABLEB_7") (pintype "passive"))
    )
    (net (code "61") (name "unconnected-(IC2-ENABLEC-Pad9)") (class "Default")
      (node (ref "IC2") (pin "9") (pinfunction "ENABLEC_9") (pintype "passive"))
    )
    (net (code "62") (name "unconnected-(IC2-ENABLED-Pad15)") (class "Default")
      (node (ref "IC2") (pin "15") (pinfunction "ENABLED_15") (pintype "passive"))
    )
    (net (code "63") (name "unconnected-(IC2-F-Pad5)") (class "Default")
      (node (ref "IC2") (pin "5") (pinfunction "F_5") (pintype "passive"))
    )
    (net (code "64") (name "unconnected-(IC2-G-Pad11)") (class "Default")
      (node (ref "IC2") (pin "11") (pinfunction "G_11") (pintype "passive"))
    )
    (net (code "65") (name "unconnected-(IC2-H-Pad13)") (class "Default")
      (node (ref "IC2") (pin "13") (pinfunction "H_13") (pintype "passive"))
    )
    (net (code "66") (name "unconnected-(IC2-NC-Pad12)") (class "Default")
      (node (ref "IC2") (pin "12") (pinfunction "NC_12") (pintype "passive"))
    )
    (net (code "67") (name "unconnected-(IC3-NC-Pad12)") (class "Default")
      (node (ref "IC3") (pin "12") (pinfunction "NC_12") (pintype "passive"))
    )
    (net (code "68") (name "unconnected-(J1-ADC-Pad12)") (class "Default")
      (node (ref "J1") (pin "12") (pinfunction "ADC_12") (pintype "passive"))
    )
    (net (code "69") (name "unconnected-(J1-ADC-Pad14)") (class "Default")
      (node (ref "J1") (pin "14") (pinfunction "ADC_14") (pintype "passive"))
    )
    (net (code "70") (name "unconnected-(J1-ADC-Pad17)") (class "Default")
      (node (ref "J1") (pin "17") (pinfunction "ADC_17") (pintype "passive"))
    )
    (net (code "71") (name "unconnected-(J1-ADC-Pad18)") (class "Default")
      (node (ref "J1") (pin "18") (pinfunction "ADC_18") (pintype "passive"))
    )
    (net (code "72") (name "unconnected-(J1-ADC-Pad20)") (class "Default")
      (node (ref "J1") (pin "20") (pinfunction "ADC_20") (pintype "passive"))
    )
    (net (code "73") (name "unconnected-(J1-ADC-Pad23)") (class "Default")
      (node (ref "J1") (pin "23") (pinfunction "ADC_23") (pintype "passive"))
    )
    (net (code "74") (name "unconnected-(J1-ADC-Pad24)") (class "Default")
      (node (ref "J1") (pin "24") (pinfunction "ADC_24") (pintype "passive"))
    )
    (net (code "75") (name "unconnected-(J1-ADC-Pad26)") (class "Default")
      (node (ref "J1") (pin "26") (pinfunction "ADC_26") (pintype "passive"))
    )
    (net (code "76") (name "unconnected-(J1-ADC-Pad27)") (class "Default")
      (node (ref "J1") (pin "27") (pinfunction "ADC_27") (pintype "passive"))
    )
    (net (code "77") (name "unconnected-(J1-ADC-Pad28)") (class "Default")
      (node (ref "J1") (pin "28") (pinfunction "ADC_28") (pintype "passive"))
    )
    (net (code "78") (name "unconnected-(J1-ADC-Pad30)") (class "Default")
      (node (ref "J1") (pin "30") (pinfunction "ADC_30") (pintype "passive"))
    )
    (net (code "79") (name "unconnected-(J1-ADC-Pad31)") (class "Default")
      (node (ref "J1") (pin "31") (pinfunction "ADC_31") (pintype "passive"))
    )
    (net (code "80") (name "unconnected-(J1-ADC-Pad33)") (class "Default")
      (node (ref "J1") (pin "33") (pinfunction "ADC_33") (pintype "passive"))
    )
    (net (code "81") (name "unconnected-(J1-ADC-Pad34)") (class "Default")
      (node (ref "J1") (pin "34") (pinfunction "ADC_34") (pintype "passive"))
    )
    (net (code "82") (name "unconnected-(J1-ADC-Pad36)") (class "Default")
      (node (ref "J1") (pin "36") (pinfunction "ADC_36") (pintype "passive"))
    )
    (net (code "83") (name "unconnected-(J1-ADC-Pad37)") (class "Default")
      (node (ref "J1") (pin "37") (pinfunction "ADC_37") (pintype "passive"))
    )
    (net (code "84") (name "unconnected-(J1-ADC-Pad39)") (class "Default")
      (node (ref "J1") (pin "39") (pinfunction "ADC_39") (pintype "passive"))
    )
    (net (code "85") (name "unconnected-(J1-ADC-Pad40)") (class "Default")
      (node (ref "J1") (pin "40") (pinfunction "ADC_40") (pintype "passive"))
    )
    (net (code "86") (name "unconnected-(J1-ADC-Pad42)") (class "Default")
      (node (ref "J1") (pin "42") (pinfunction "ADC_42") (pintype "passive"))
    )
    (net (code "87") (name "unconnected-(J1-ADC{slash}CMP+-Pad15)") (class "Default")
      (node (ref "J1") (pin "15") (pinfunction "ADC/CMP+_15") (pintype "passive"))
    )
    (net (code "88") (name "unconnected-(J1-ADC{slash}CMP+-Pad21)") (class "Default")
      (node (ref "J1") (pin "21") (pinfunction "ADC/CMP+_21") (pintype "passive"))
    )
    (net (code "89") (name "unconnected-(J1-ADC{slash}CMP+-Pad25)") (class "Default")
      (node (ref "J1") (pin "25") (pinfunction "ADC/CMP+_25") (pintype "passive"))
    )
    (net (code "90") (name "unconnected-(J1-GPIO-Pad58)") (class "Default")
      (node (ref "J1") (pin "58") (pinfunction "GPIO_58") (pintype "passive"))
    )
    (net (code "91") (name "unconnected-(J1-GPIO-Pad60)") (class "Default")
      (node (ref "J1") (pin "60") (pinfunction "GPIO_60") (pintype "passive"))
    )
    (net (code "92") (name "unconnected-(J1-GPIO-Pad62)") (class "Default")
      (node (ref "J1") (pin "62") (pinfunction "GPIO_62") (pintype "passive"))
    )
    (net (code "93") (name "unconnected-(J1-GPIO-Pad64)") (class "Default")
      (node (ref "J1") (pin "64") (pinfunction "GPIO_64") (pintype "passive"))
    )
    (net (code "94") (name "unconnected-(J1-GPIO-Pad75)") (class "Default")
      (node (ref "J1") (pin "75") (pinfunction "GPIO_75") (pintype "passive"))
    )
    (net (code "95") (name "unconnected-(J1-GPIO-Pad77)") (class "Default")
      (node (ref "J1") (pin "77") (pinfunction "GPIO_77") (pintype "passive"))
    )
    (net (code "96") (name "unconnected-(J1-GPIO-Pad79)") (class "Default")
      (node (ref "J1") (pin "79") (pinfunction "GPIO_79") (pintype "passive"))
    )
    (net (code "97") (name "unconnected-(J1-GPIO-Pad81)") (class "Default")
      (node (ref "J1") (pin "81") (pinfunction "GPIO_81") (pintype "passive"))
    )
    (net (code "98") (name "unconnected-(J1-GPIO-Pad86)") (class "Default")
      (node (ref "J1") (pin "86") (pinfunction "GPIO_86") (pintype "passive"))
    )
    (net (code "99") (name "unconnected-(J1-GPIO-Pad88)") (class "Default")
      (node (ref "J1") (pin "88") (pinfunction "GPIO_88") (pintype "passive"))
    )
    (net (code "100") (name "unconnected-(J1-GPIO-Pad89)") (class "Default")
      (node (ref "J1") (pin "89") (pinfunction "GPIO_89") (pintype "passive"))
    )
    (net (code "101") (name "unconnected-(J1-GPIO-Pad90)") (class "Default")
      (node (ref "J1") (pin "90") (pinfunction "GPIO_90") (pintype "passive"))
    )
    (net (code "102") (name "unconnected-(J1-GPIO-Pad91)") (class "Default")
      (node (ref "J1") (pin "91") (pinfunction "GPIO_91") (pintype "passive"))
    )
    (net (code "103") (name "unconnected-(J1-GPIO-Pad92)") (class "Default")
      (node (ref "J1") (pin "92") (pinfunction "GPIO_92") (pintype "passive"))
    )
    (net (code "104") (name "unconnected-(J1-GPIO-Pad93)") (class "Default")
      (node (ref "J1") (pin "93") (pinfunction "GPIO_93") (pintype "passive"))
    )
    (net (code "105") (name "unconnected-(J1-GPIO-Pad94)") (class "Default")
      (node (ref "J1") (pin "94") (pinfunction "GPIO_94") (pintype "passive"))
    )
    (net (code "106") (name "unconnected-(J1-GPIO-Pad95)") (class "Default")
      (node (ref "J1") (pin "95") (pinfunction "GPIO_95") (pintype "passive"))
    )
    (net (code "107") (name "unconnected-(J1-GPIO-Pad96)") (class "Default")
      (node (ref "J1") (pin "96") (pinfunction "GPIO_96") (pintype "passive"))
    )
    (net (code "108") (name "unconnected-(J1-GPIO-Pad99)") (class "Default")
      (node (ref "J1") (pin "99") (pinfunction "GPIO_99") (pintype "passive"))
    )
    (net (code "109") (name "unconnected-(J1-GPIO-Pad100)") (class "Default")
      (node (ref "J1") (pin "100") (pinfunction "GPIO_100") (pintype "passive"))
    )
    (net (code "110") (name "unconnected-(J1-GPIO-Pad101)") (class "Default")
      (node (ref "J1") (pin "101") (pinfunction "GPIO_101") (pintype "passive"))
    )
    (net (code "111") (name "unconnected-(J1-GPIO-Pad102)") (class "Default")
      (node (ref "J1") (pin "102") (pinfunction "GPIO_102") (pintype "passive"))
    )
    (net (code "112") (name "unconnected-(J1-GPIO-Pad103)") (class "Default")
      (node (ref "J1") (pin "103") (pinfunction "GPIO_103") (pintype "passive"))
    )
    (net (code "113") (name "unconnected-(J1-GPIO-Pad104)") (class "Default")
      (node (ref "J1") (pin "104") (pinfunction "GPIO_104") (pintype "passive"))
    )
    (net (code "114") (name "unconnected-(J1-GPIO-Pad105)") (class "Default")
      (node (ref "J1") (pin "105") (pinfunction "GPIO_105") (pintype "passive"))
    )
    (net (code "115") (name "unconnected-(J1-GPIO-Pad106)") (class "Default")
      (node (ref "J1") (pin "106") (pinfunction "GPIO_106") (pintype "passive"))
    )
    (net (code "116") (name "unconnected-(J1-GPIO-Pad107)") (class "Default")
      (node (ref "J1") (pin "107") (pinfunction "GPIO_107") (pintype "passive"))
    )
    (net (code "117") (name "unconnected-(J1-GPIO-Pad108)") (class "Default")
      (node (ref "J1") (pin "108") (pinfunction "GPIO_108") (pintype "passive"))
    )
    (net (code "118") (name "unconnected-(J1-GPIO-Pad109)") (class "Default")
      (node (ref "J1") (pin "109") (pinfunction "GPIO_109") (pintype "passive"))
    )
    (net (code "119") (name "unconnected-(J1-GPIO-Pad110)") (class "Default")
      (node (ref "J1") (pin "110") (pinfunction "GPIO_110") (pintype "passive"))
    )
    (net (code "120") (name "unconnected-(J1-GPIO-Pad121)") (class "Default")
      (node (ref "J1") (pin "121") (pinfunction "GPIO_121") (pintype "passive"))
    )
    (net (code "121") (name "unconnected-(J1-GPIO-Pad122)") (class "Default")
      (node (ref "J1") (pin "122") (pinfunction "GPIO_122") (pintype "passive"))
    )
    (net (code "122") (name "unconnected-(J1-GPIO-Pad123)") (class "Default")
      (node (ref "J1") (pin "123") (pinfunction "GPIO_123") (pintype "passive"))
    )
    (net (code "123") (name "unconnected-(J1-GPIO-Pad124)") (class "Default")
      (node (ref "J1") (pin "124") (pinfunction "GPIO_124") (pintype "passive"))
    )
    (net (code "124") (name "unconnected-(J1-GPIO-Pad125)") (class "Default")
      (node (ref "J1") (pin "125") (pinfunction "GPIO_125") (pintype "passive"))
    )
    (net (code "125") (name "unconnected-(J1-GPIO-Pad126)") (class "Default")
      (node (ref "J1") (pin "126") (pinfunction "GPIO_126") (pintype "passive"))
    )
    (net (code "126") (name "unconnected-(J1-GPIO-Pad127)") (class "Default")
      (node (ref "J1") (pin "127") (pinfunction "GPIO_127") (pintype "passive"))
    )
    (net (code "127") (name "unconnected-(J1-GPIO-Pad128)") (class "Default")
      (node (ref "J1") (pin "128") (pinfunction "GPIO_128") (pintype "passive"))
    )
    (net (code "128") (name "unconnected-(J1-GPIO-Pad129)") (class "Default")
      (node (ref "J1") (pin "129") (pinfunction "GPIO_129") (pintype "passive"))
    )
    (net (code "129") (name "unconnected-(J1-GPIO-Pad130)") (class "Default")
      (node (ref "J1") (pin "130") (pinfunction "GPIO_130") (pintype "passive"))
    )
    (net (code "130") (name "unconnected-(J1-GPIO-Pad131)") (class "Default")
      (node (ref "J1") (pin "131") (pinfunction "GPIO_131") (pintype "passive"))
    )
    (net (code "131") (name "unconnected-(J1-GPIO-Pad132)") (class "Default")
      (node (ref "J1") (pin "132") (pinfunction "GPIO_132") (pintype "passive"))
    )
    (net (code "132") (name "unconnected-(J1-GPIO-Pad133)") (class "Default")
      (node (ref "J1") (pin "133") (pinfunction "GPIO_133") (pintype "passive"))
    )
    (net (code "133") (name "unconnected-(J1-GPIO-Pad134)") (class "Default")
      (node (ref "J1") (pin "134") (pinfunction "GPIO_134") (pintype "passive"))
    )
    (net (code "134") (name "unconnected-(J1-GPIO-Pad137)") (class "Default")
      (node (ref "J1") (pin "137") (pinfunction "GPIO_137") (pintype "passive"))
    )
    (net (code "135") (name "unconnected-(J1-GPIO-Pad138)") (class "Default")
      (node (ref "J1") (pin "138") (pinfunction "GPIO_138") (pintype "passive"))
    )
    (net (code "136") (name "unconnected-(J1-GPIO-Pad139)") (class "Default")
      (node (ref "J1") (pin "139") (pinfunction "GPIO_139") (pintype "passive"))
    )
    (net (code "137") (name "unconnected-(J1-GPIO-Pad140)") (class "Default")
      (node (ref "J1") (pin "140") (pinfunction "GPIO_140") (pintype "passive"))
    )
    (net (code "138") (name "unconnected-(J1-GPIO-Pad141)") (class "Default")
      (node (ref "J1") (pin "141") (pinfunction "GPIO_141") (pintype "passive"))
    )
    (net (code "139") (name "unconnected-(J1-GPIO-Pad142)") (class "Default")
      (node (ref "J1") (pin "142") (pinfunction "GPIO_142") (pintype "passive"))
    )
    (net (code "140") (name "unconnected-(J1-GPIO-Pad143)") (class "Default")
      (node (ref "J1") (pin "143") (pinfunction "GPIO_143") (pintype "passive"))
    )
    (net (code "141") (name "unconnected-(J1-GPIO-Pad144)") (class "Default")
      (node (ref "J1") (pin "144") (pinfunction "GPIO_144") (pintype "passive"))
    )
    (net (code "142") (name "unconnected-(J1-GPIO-Pad145)") (class "Default")
      (node (ref "J1") (pin "145") (pinfunction "GPIO_145") (pintype "passive"))
    )
    (net (code "143") (name "unconnected-(J1-GPIO-Pad146)") (class "Default")
      (node (ref "J1") (pin "146") (pinfunction "GPIO_146") (pintype "passive"))
    )
    (net (code "144") (name "unconnected-(J1-GPIO-Pad147)") (class "Default")
      (node (ref "J1") (pin "147") (pinfunction "GPIO_147") (pintype "passive"))
    )
    (net (code "145") (name "unconnected-(J1-GPIO-Pad148)") (class "Default")
      (node (ref "J1") (pin "148") (pinfunction "GPIO_148") (pintype "passive"))
    )
    (net (code "146") (name "unconnected-(J1-GPIO-Pad149)") (class "Default")
      (node (ref "J1") (pin "149") (pinfunction "GPIO_149") (pintype "passive"))
    )
    (net (code "147") (name "unconnected-(J1-GPIO-Pad150)") (class "Default")
      (node (ref "J1") (pin "150") (pinfunction "GPIO_150") (pintype "passive"))
    )
    (net (code "148") (name "unconnected-(J1-GPIO-Pad151)") (class "Default")
      (node (ref "J1") (pin "151") (pinfunction "GPIO_151") (pintype "passive"))
    )
    (net (code "149") (name "unconnected-(J1-GPIO-Pad152)") (class "Default")
      (node (ref "J1") (pin "152") (pinfunction "GPIO_152") (pintype "passive"))
    )
    (net (code "150") (name "unconnected-(J1-GPIO-Pad153)") (class "Default")
      (node (ref "J1") (pin "153") (pinfunction "GPIO_153") (pintype "passive"))
    )
    (net (code "151") (name "unconnected-(J1-GPIO-Pad154)") (class "Default")
      (node (ref "J1") (pin "154") (pinfunction "GPIO_154") (pintype "passive"))
    )
    (net (code "152") (name "unconnected-(J1-GPIO-Pad155)") (class "Default")
      (node (ref "J1") (pin "155") (pinfunction "GPIO_155") (pintype "passive"))
    )
    (net (code "153") (name "unconnected-(J1-GPIO-Pad156)") (class "Default")
      (node (ref "J1") (pin "156") (pinfunction "GPIO_156") (pintype "passive"))
    )
    (net (code "154") (name "unconnected-(J1-GPIO-Pad159)") (class "Default")
      (node (ref "J1") (pin "159") (pinfunction "GPIO_159") (pintype "passive"))
    )
    (net (code "155") (name "unconnected-(J1-GPIO-Pad160)") (class "Default")
      (node (ref "J1") (pin "160") (pinfunction "GPIO_160") (pintype "passive"))
    )
    (net (code "156") (name "unconnected-(J1-GPIO-Pad161)") (class "Default")
      (node (ref "J1") (pin "161") (pinfunction "GPIO_161") (pintype "passive"))
    )
    (net (code "157") (name "unconnected-(J1-GPIO-Pad162)") (class "Default")
      (node (ref "J1") (pin "162") (pinfunction "GPIO_162") (pintype "passive"))
    )
    (net (code "158") (name "unconnected-(J1-GPIO-Pad163)") (class "Default")
      (node (ref "J1") (pin "163") (pinfunction "GPIO_163") (pintype "passive"))
    )
    (net (code "159") (name "unconnected-(J1-GPIO-Pad164)") (class "Default")
      (node (ref "J1") (pin "164") (pinfunction "GPIO_164") (pintype "passive"))
    )
    (net (code "160") (name "unconnected-(J1-GPIO-Pad165)") (class "Default")
      (node (ref "J1") (pin "165") (pinfunction "GPIO_165") (pintype "passive"))
    )
    (net (code "161") (name "unconnected-(J1-GPIO-Pad166)") (class "Default")
      (node (ref "J1") (pin "166") (pinfunction "GPIO_166") (pintype "passive"))
    )
    (net (code "162") (name "unconnected-(J1-GPIO-Pad167)") (class "Default")
      (node (ref "J1") (pin "167") (pinfunction "GPIO_167") (pintype "passive"))
    )
    (net (code "163") (name "unconnected-(J1-GPIO-Pad168)") (class "Default")
      (node (ref "J1") (pin "168") (pinfunction "GPIO_168") (pintype "passive"))
    )
    (net (code "164") (name "unconnected-(J1-GPIO-Pad169)") (class "Default")
      (node (ref "J1") (pin "169") (pinfunction "GPIO_169") (pintype "passive"))
    )
    (net (code "165") (name "unconnected-(J1-GPIO-Pad170)") (class "Default")
      (node (ref "J1") (pin "170") (pinfunction "GPIO_170") (pintype "passive"))
    )
    (net (code "166") (name "unconnected-(J1-I2CSCLA-Pad87)") (class "Default")
      (node (ref "J1") (pin "87") (pinfunction "I2CSCLA_87") (pintype "passive"))
    )
    (net (code "167") (name "unconnected-(J1-I2CSDAA-Pad85)") (class "Default")
      (node (ref "J1") (pin "85") (pinfunction "I2CSDAA_85") (pintype "passive"))
    )
    (net (code "168") (name "unconnected-(J1-JTAG-EMU0-Pad2)") (class "Default")
      (node (ref "J1") (pin "2") (pinfunction "JTAG-EMU0_2") (pintype "passive"))
    )
    (net (code "169") (name "unconnected-(J1-JTAG-EMU1-Pad1)") (class "Default")
      (node (ref "J1") (pin "1") (pinfunction "JTAG-EMU1_1") (pintype "passive"))
    )
    (net (code "170") (name "unconnected-(J1-JTAG-TCK-Pad5)") (class "Default")
      (node (ref "J1") (pin "5") (pinfunction "JTAG-TCK_5") (pintype "passive"))
    )
    (net (code "171") (name "unconnected-(J1-JTAG-TDI-Pad8)") (class "Default")
      (node (ref "J1") (pin "8") (pinfunction "JTAG-TDI_8") (pintype "passive"))
    )
    (net (code "172") (name "unconnected-(J1-JTAG-TDO-Pad6)") (class "Default")
      (node (ref "J1") (pin "6") (pinfunction "JTAG-TDO_6") (pintype "passive"))
    )
    (net (code "173") (name "unconnected-(J1-JTAG-TMS-Pad3)") (class "Default")
      (node (ref "J1") (pin "3") (pinfunction "JTAG-TMS_3") (pintype "passive"))
    )
    (net (code "174") (name "unconnected-(J1-JTAG-TRS~{T}-Pad4)") (class "Default")
      (node (ref "J1") (pin "4") (pinfunction "JTAG-TRS~{T}_4") (pintype "passive"))
    )
    (net (code "175") (name "unconnected-(J1-PWM1A-Pad49)") (class "Default")
      (node (ref "J1") (pin "49") (pinfunction "PWM1A_49") (pintype "passive"))
    )
    (net (code "176") (name "unconnected-(J1-PWM1B-Pad51)") (class "Default")
      (node (ref "J1") (pin "51") (pinfunction "PWM1B_51") (pintype "passive"))
    )
    (net (code "177") (name "unconnected-(J1-PWM2A-Pad53)") (class "Default")
      (node (ref "J1") (pin "53") (pinfunction "PWM2A_53") (pintype "passive"))
    )
    (net (code "178") (name "unconnected-(J1-PWM2B-Pad55)") (class "Default")
      (node (ref "J1") (pin "55") (pinfunction "PWM2B_55") (pintype "passive"))
    )
    (net (code "179") (name "unconnected-(J1-PWM3A-Pad50)") (class "Default")
      (node (ref "J1") (pin "50") (pinfunction "PWM3A_50") (pintype "passive"))
    )
    (net (code "180") (name "unconnected-(J1-PWM3B-Pad52)") (class "Default")
      (node (ref "J1") (pin "52") (pinfunction "PWM3B_52") (pintype "passive"))
    )
    (net (code "181") (name "unconnected-(J1-PWM4A-Pad54)") (class "Default")
      (node (ref "J1") (pin "54") (pinfunction "PWM4A_54") (pintype "passive"))
    )
    (net (code "182") (name "unconnected-(J1-PWM4B-Pad56)") (class "Default")
      (node (ref "J1") (pin "56") (pinfunction "PWM4B_56") (pintype "passive"))
    )
    (net (code "183") (name "unconnected-(J1-PWM5A-Pad57)") (class "Default")
      (node (ref "J1") (pin "57") (pinfunction "PWM5A_57") (pintype "passive"))
    )
    (net (code "184") (name "unconnected-(J1-PWM5B-Pad59)") (class "Default")
      (node (ref "J1") (pin "59") (pinfunction "PWM5B_59") (pintype "passive"))
    )
    (net (code "185") (name "unconnected-(J1-PWM6A-Pad61)") (class "Default")
      (node (ref "J1") (pin "61") (pinfunction "PWM6A_61") (pintype "passive"))
    )
    (net (code "186") (name "unconnected-(J1-PWM6B-Pad63)") (class "Default")
      (node (ref "J1") (pin "63") (pinfunction "PWM6B_63") (pintype "passive"))
    )
    (net (code "187") (name "unconnected-(J1-QEP1-I-Pad74)") (class "Default")
      (node (ref "J1") (pin "74") (pinfunction "QEP1-I_74") (pintype "passive"))
    )
    (net (code "188") (name "unconnected-(J1-QEP1-S-Pad72)") (class "Default")
      (node (ref "J1") (pin "72") (pinfunction "QEP1-S_72") (pintype "passive"))
    )
    (net (code "189") (name "unconnected-(J1-RESE~{T}-Pad120)") (class "Default")
      (node (ref "J1") (pin "120") (pinfunction "RESE~{T}_120") (pintype "passive"))
    )
    (net (code "190") (name "unconnected-(J1-RSV-Pad13)") (class "Default")
      (node (ref "J1") (pin "13") (pinfunction "RSV_13") (pintype "passive"))
    )
    (net (code "191") (name "unconnected-(J1-RSV-Pad16)") (class "Default")
      (node (ref "J1") (pin "16") (pinfunction "RSV_16") (pintype "passive"))
    )
    (net (code "192") (name "unconnected-(J1-RSV-Pad29)") (class "Default")
      (node (ref "J1") (pin "29") (pinfunction "RSV_29") (pintype "passive"))
    )
    (net (code "193") (name "unconnected-(J1-RSV-Pad32)") (class "Default")
      (node (ref "J1") (pin "32") (pinfunction "RSV_32") (pintype "passive"))
    )
    (net (code "194") (name "unconnected-(J1-RSV-Pad41)") (class "Default")
      (node (ref "J1") (pin "41") (pinfunction "RSV_41") (pintype "passive"))
    )
    (net (code "195") (name "unconnected-(J1-RSV-Pad43)") (class "Default")
      (node (ref "J1") (pin "43") (pinfunction "RSV_43") (pintype "passive"))
    )
    (net (code "196") (name "unconnected-(J1-RSV-Pad44)") (class "Default")
      (node (ref "J1") (pin "44") (pinfunction "RSV_44") (pintype "passive"))
    )
    (net (code "197") (name "unconnected-(J1-RSV-Pad66)") (class "Default")
      (node (ref "J1") (pin "66") (pinfunction "RSV_66") (pintype "passive"))
    )
    (net (code "198") (name "unconnected-(J1-RSV-Pad113)") (class "Default")
      (node (ref "J1") (pin "113") (pinfunction "RSV_113") (pintype "passive"))
    )
    (net (code "199") (name "unconnected-(J1-RSV-Pad114)") (class "Default")
      (node (ref "J1") (pin "114") (pinfunction "RSV_114") (pintype "passive"))
    )
    (net (code "200") (name "unconnected-(J1-RSV-Pad115)") (class "Default")
      (node (ref "J1") (pin "115") (pinfunction "RSV_115") (pintype "passive"))
    )
    (net (code "201") (name "unconnected-(J1-RSV-Pad116)") (class "Default")
      (node (ref "J1") (pin "116") (pinfunction "RSV_116") (pintype "passive"))
    )
    (net (code "202") (name "unconnected-(J1-RSV-Pad117)") (class "Default")
      (node (ref "J1") (pin "117") (pinfunction "RSV_117") (pintype "passive"))
    )
    (net (code "203") (name "unconnected-(J1-RSV-Pad118)") (class "Default")
      (node (ref "J1") (pin "118") (pinfunction "RSV_118") (pintype "passive"))
    )
    (net (code "204") (name "unconnected-(J1-RSV-Pad119)") (class "Default")
      (node (ref "J1") (pin "119") (pinfunction "RSV_119") (pintype "passive"))
    )
    (net (code "205") (name "unconnected-(J1-RSV-Pad136)") (class "Default")
      (node (ref "J1") (pin "136") (pinfunction "RSV_136") (pintype "passive"))
    )
    (net (code "206") (name "unconnected-(J1-RSV-Pad171)") (class "Default")
      (node (ref "J1") (pin "171") (pinfunction "RSV_171") (pintype "passive"))
    )
    (net (code "207") (name "unconnected-(J1-RSV-Pad172)") (class "Default")
      (node (ref "J1") (pin "172") (pinfunction "RSV_172") (pintype "passive"))
    )
    (net (code "208") (name "unconnected-(J1-RSV-Pad173)") (class "Default")
      (node (ref "J1") (pin "173") (pinfunction "RSV_173") (pintype "passive"))
    )
    (net (code "209") (name "unconnected-(J1-RSV-Pad174)") (class "Default")
      (node (ref "J1") (pin "174") (pinfunction "RSV_174") (pintype "passive"))
    )
    (net (code "210") (name "unconnected-(J1-RSV-Pad175)") (class "Default")
      (node (ref "J1") (pin "175") (pinfunction "RSV_175") (pintype "passive"))
    )
    (net (code "211") (name "unconnected-(J1-RSV-Pad176)") (class "Default")
      (node (ref "J1") (pin "176") (pinfunction "RSV_176") (pintype "passive"))
    )
    (net (code "212") (name "unconnected-(J1-RSV-Pad177)") (class "Default")
      (node (ref "J1") (pin "177") (pinfunction "RSV_177") (pintype "passive"))
    )
    (net (code "213") (name "unconnected-(J1-RSV-Pad178)") (class "Default")
      (node (ref "J1") (pin "178") (pinfunction "RSV_178") (pintype "passive"))
    )
    (net (code "214") (name "unconnected-(J1-VREFHI-Pad45)") (class "Default")
      (node (ref "J1") (pin "45") (pinfunction "VREFHI_45") (pintype "passive"))
    )
    (net (code "215") (name "unconnected-(Rx1-6-Pad8)") (class "Default")
      (node (ref "Rx1") (pin "8") (pinfunction "6_8") (pintype "passive"))
    )
    (net (code "216") (name "unconnected-(Rx1-Pad5)") (class "Default")
      (node (ref "Rx1") (pin "5") (pinfunction "5_5") (pintype "passive"))
    )
    (net (code "217") (name "unconnected-(Rx2-6-Pad8)") (class "Default")
      (node (ref "Rx2") (pin "8") (pinfunction "6_8") (pintype "passive"))
    )
    (net (code "218") (name "unconnected-(Rx2-Pad5)") (class "Default")
      (node (ref "Rx2") (pin "5") (pinfunction "5_5") (pintype "passive"))
    )
    (net (code "219") (name "unconnected-(Rx3-6-Pad8)") (class "Default")
      (node (ref "Rx3") (pin "8") (pinfunction "6_8") (pintype "passive"))
    )
    (net (code "220") (name "unconnected-(Rx3-Pad5)") (class "Default")
      (node (ref "Rx3") (pin "5") (pinfunction "5_5") (pintype "passive"))
    )
    (net (code "221") (name "unconnected-(Rx4-6-Pad8)") (class "Default")
      (node (ref "Rx4") (pin "8") (pinfunction "6_8") (pintype "passive"))
    )
    (net (code "222") (name "unconnected-(Rx4-Pad5)") (class "Default")
      (node (ref "Rx4") (pin "5") (pinfunction "5_5") (pintype "passive"))
    )
    (net (code "223") (name "unconnected-(Rx5-6-Pad8)") (class "Default")
      (node (ref "Rx5") (pin "8") (pinfunction "6_8") (pintype "passive"))
    )
    (net (code "224") (name "unconnected-(Rx5-Pad5)") (class "Default")
      (node (ref "Rx5") (pin "5") (pinfunction "5_5") (pintype "passive"))
    )
    (net (code "225") (name "unconnected-(Rx6-6-Pad8)") (class "Default")
      (node (ref "Rx6") (pin "8") (pinfunction "6_8") (pintype "passive"))
    )
    (net (code "226") (name "unconnected-(Rx6-Pad5)") (class "Default")
      (node (ref "Rx6") (pin "5") (pinfunction "5_5") (pintype "passive"))
    )
    (net (code "227") (name "unconnected-(Rx7-6-Pad8)") (class "Default")
      (node (ref "Rx7") (pin "8") (pinfunction "6_8") (pintype "passive"))
    )
    (net (code "228") (name "unconnected-(Rx7-Pad5)") (class "Default")
      (node (ref "Rx7") (pin "5") (pinfunction "5_5") (pintype "passive"))
    )
    (net (code "229") (name "unconnected-(Rx8-6-Pad8)") (class "Default")
      (node (ref "Rx8") (pin "8") (pinfunction "6_8") (pintype "passive"))
    )
    (net (code "230") (name "unconnected-(Rx8-Pad5)") (class "Default")
      (node (ref "Rx8") (pin "5") (pinfunction "5_5") (pintype "passive"))
    )
    (net (code "231") (name "unconnected-(Rx9-6-Pad8)") (class "Default")
      (node (ref "Rx9") (pin "8") (pinfunction "6_8") (pintype "passive"))
    )
    (net (code "232") (name "unconnected-(Rx9-Pad5)") (class "Default")
      (node (ref "Rx9") (pin "5") (pinfunction "5_5") (pintype "passive"))
    )
    (net (code "233") (name "unconnected-(Tx1-6-Pad8)") (class "Default")
      (node (ref "Tx1") (pin "8") (pinfunction "6_8") (pintype "passive"))
    )
    (net (code "234") (name "unconnected-(Tx1-Pad3)") (class "Default")
      (node (ref "Tx1") (pin "3") (pinfunction "3_3") (pintype "passive"))
    )
    (net (code "235") (name "unconnected-(Tx1-Pad4)") (class "Default")
      (node (ref "Tx1") (pin "4") (pinfunction "4_4") (pintype "passive"))
    )
    (net (code "236") (name "unconnected-(Tx1-Pad5)") (class "Default")
      (node (ref "Tx1") (pin "5") (pinfunction "5_5") (pintype "passive"))
    )
    (net (code "237") (name "unconnected-(Tx2-6-Pad8)") (class "Default")
      (node (ref "Tx2") (pin "8") (pinfunction "6_8") (pintype "passive"))
    )
    (net (code "238") (name "unconnected-(Tx2-Pad3)") (class "Default")
      (node (ref "Tx2") (pin "3") (pinfunction "3_3") (pintype "passive"))
    )
    (net (code "239") (name "unconnected-(Tx2-Pad4)") (class "Default")
      (node (ref "Tx2") (pin "4") (pinfunction "4_4") (pintype "passive"))
    )
    (net (code "240") (name "unconnected-(Tx2-Pad5)") (class "Default")
      (node (ref "Tx2") (pin "5") (pinfunction "5_5") (pintype "passive"))
    )
    (net (code "241") (name "unconnected-(Tx3-6-Pad8)") (class "Default")
      (node (ref "Tx3") (pin "8") (pinfunction "6_8") (pintype "passive"))
    )
    (net (code "242") (name "unconnected-(Tx3-Pad3)") (class "Default")
      (node (ref "Tx3") (pin "3") (pinfunction "3_3") (pintype "passive"))
    )
    (net (code "243") (name "unconnected-(Tx3-Pad4)") (class "Default")
      (node (ref "Tx3") (pin "4") (pinfunction "4_4") (pintype "passive"))
    )
    (net (code "244") (name "unconnected-(Tx3-Pad5)") (class "Default")
      (node (ref "Tx3") (pin "5") (pinfunction "5_5") (pintype "passive"))
    )
    (net (code "245") (name "unconnected-(Tx4-6-Pad8)") (class "Default")
      (node (ref "Tx4") (pin "8") (pinfunction "6_8") (pintype "passive"))
    )
    (net (code "246") (name "unconnected-(Tx4-Pad3)") (class "Default")
      (node (ref "Tx4") (pin "3") (pinfunction "3_3") (pintype "passive"))
    )
    (net (code "247") (name "unconnected-(Tx4-Pad4)") (class "Default")
      (node (ref "Tx4") (pin "4") (pinfunction "4_4") (pintype "passive"))
    )
    (net (code "248") (name "unconnected-(Tx4-Pad5)") (class "Default")
      (node (ref "Tx4") (pin "5") (pinfunction "5_5") (pintype "passive"))
    )
    (net (code "249") (name "unconnected-(Tx5-6-Pad8)") (class "Default")
      (node (ref "Tx5") (pin "8") (pinfunction "6_8") (pintype "passive"))
    )
    (net (code "250") (name "unconnected-(Tx5-Pad3)") (class "Default")
      (node (ref "Tx5") (pin "3") (pinfunction "3_3") (pintype "passive"))
    )
    (net (code "251") (name "unconnected-(Tx5-Pad4)") (class "Default")
      (node (ref "Tx5") (pin "4") (pinfunction "4_4") (pintype "passive"))
    )
    (net (code "252") (name "unconnected-(Tx5-Pad5)") (class "Default")
      (node (ref "Tx5") (pin "5") (pinfunction "5_5") (pintype "passive"))
    )
    (net (code "253") (name "unconnected-(Tx6-6-Pad8)") (class "Default")
      (node (ref "Tx6") (pin "8") (pinfunction "6_8") (pintype "passive"))
    )
    (net (code "254") (name "unconnected-(Tx6-Pad3)") (class "Default")
      (node (ref "Tx6") (pin "3") (pinfunction "3_3") (pintype "passive"))
    )
    (net (code "255") (name "unconnected-(Tx6-Pad4)") (class "Default")
      (node (ref "Tx6") (pin "4") (pinfunction "4_4") (pintype "passive"))
    )
    (net (code "256") (name "unconnected-(Tx6-Pad5)") (class "Default")
      (node (ref "Tx6") (pin "5") (pinfunction "5_5") (pintype "passive"))
    )
    (net (code "257") (name "unconnected-(Tx7-6-Pad8)") (class "Default")
      (node (ref "Tx7") (pin "8") (pinfunction "6_8") (pintype "passive"))
    )
    (net (code "258") (name "unconnected-(Tx7-Pad3)") (class "Default")
      (node (ref "Tx7") (pin "3") (pinfunction "3_3") (pintype "passive"))
    )
    (net (code "259") (name "unconnected-(Tx7-Pad4)") (class "Default")
      (node (ref "Tx7") (pin "4") (pinfunction "4_4") (pintype "passive"))
    )
    (net (code "260") (name "unconnected-(Tx7-Pad5)") (class "Default")
      (node (ref "Tx7") (pin "5") (pinfunction "5_5") (pintype "passive"))
    )
    (net (code "261") (name "unconnected-(Tx8-6-Pad8)") (class "Default")
      (node (ref "Tx8") (pin "8") (pinfunction "6_8") (pintype "passive"))
    )
    (net (code "262") (name "unconnected-(Tx8-Pad3)") (class "Default")
      (node (ref "Tx8") (pin "3") (pinfunction "3_3") (pintype "passive"))
    )
    (net (code "263") (name "unconnected-(Tx8-Pad4)") (class "Default")
      (node (ref "Tx8") (pin "4") (pinfunction "4_4") (pintype "passive"))
    )
    (net (code "264") (name "unconnected-(Tx8-Pad5)") (class "Default")
      (node (ref "Tx8") (pin "5") (pinfunction "5_5") (pintype "passive"))
    )
    (net (code "265") (name "unconnected-(Tx9-6-Pad8)") (class "Default")
      (node (ref "Tx9") (pin "8") (pinfunction "6_8") (pintype "passive"))
    )
    (net (code "266") (name "unconnected-(Tx9-Pad3)") (class "Default")
      (node (ref "Tx9") (pin "3") (pinfunction "3_3") (pintype "passive"))
    )
    (net (code "267") (name "unconnected-(Tx9-Pad4)") (class "Default")
      (node (ref "Tx9") (pin "4") (pinfunction "4_4") (pintype "passive"))
    )
    (net (code "268") (name "unconnected-(Tx9-Pad5)") (class "Default")
      (node (ref "Tx9") (pin "5") (pinfunction "5_5") (pintype "passive"))
    )
    (net (code "269") (name "unconnected-(U2-Pad3)") (class "Default")
      (node (ref "U2") (pin "3") (pinfunction "3_3") (pintype "passive"))
    )
    (net (code "270") (name "unconnected-(U2-Pad6)") (class "Default")
      (node (ref "U2") (pin "6") (pinfunction "6_6") (pintype "passive"))
    )
    (net (code "271") (name "unconnected-(U2-Pad7)") (class "Default")
      (node (ref "U2") (pin "7") (pinfunction "7_7") (pintype "passive"))
    )
    (net (code "272") (name "unconnected-(U2-Pad8)") (class "Default")
      (node (ref "U2") (pin "8") (pinfunction "8_8") (pintype "passive"))
    )
    (net (code "273") (name "unconnected-(U2-Pad10)") (class "Default")
      (node (ref "U2") (pin "10") (pinfunction "10_10") (pintype "passive"))
    )
    (net (code "274") (name "unconnected-(U4-Pad3)") (class "Default")
      (node (ref "U4") (pin "3") (pinfunction "3_3") (pintype "passive"))
    )
    (net (code "275") (name "unconnected-(U4-Pad6)") (class "Default")
      (node (ref "U4") (pin "6") (pinfunction "6_6") (pintype "passive"))
    )
    (net (code "276") (name "unconnected-(U4-Pad7)") (class "Default")
      (node (ref "U4") (pin "7") (pinfunction "7_7") (pintype "passive"))
    )
    (net (code "277") (name "unconnected-(U4-Pad8)") (class "Default")
      (node (ref "U4") (pin "8") (pinfunction "8_8") (pintype "passive"))
    )
    (net (code "278") (name "unconnected-(U4-Pad10)") (class "Default")
      (node (ref "U4") (pin "10") (pinfunction "10_10") (pintype "passive"))
    )
    (net (code "279") (name "unconnected-(U5-Pad3)") (class "Default")
      (node (ref "U5") (pin "3") (pinfunction "3_3") (pintype "passive"))
    )
    (net (code "280") (name "unconnected-(U5-Pad6)") (class "Default")
      (node (ref "U5") (pin "6") (pinfunction "6_6") (pintype "passive"))
    )
    (net (code "281") (name "unconnected-(U5-Pad7)") (class "Default")
      (node (ref "U5") (pin "7") (pinfunction "7_7") (pintype "passive"))
    )
    (net (code "282") (name "unconnected-(U5-Pad8)") (class "Default")
      (node (ref "U5") (pin "8") (pinfunction "8_8") (pintype "passive"))
    )
    (net (code "283") (name "unconnected-(U5-Pad10)") (class "Default")
      (node (ref "U5") (pin "10") (pinfunction "10_10") (pintype "passive"))
    )
    (net (code "284") (name "unconnected-(U6-Pad3)") (class "Default")
      (node (ref "U6") (pin "3") (pinfunction "3_3") (pintype "passive"))
    )
    (net (code "285") (name "unconnected-(U6-Pad6)") (class "Default")
      (node (ref "U6") (pin "6") (pinfunction "6_6") (pintype "passive"))
    )
    (net (code "286") (name "unconnected-(U6-Pad7)") (class "Default")
      (node (ref "U6") (pin "7") (pinfunction "7_7") (pintype "passive"))
    )
    (net (code "287") (name "unconnected-(U6-Pad8)") (class "Default")
      (node (ref "U6") (pin "8") (pinfunction "8_8") (pintype "passive"))
    )
    (net (code "288") (name "unconnected-(U6-Pad10)") (class "Default")
      (node (ref "U6") (pin "10") (pinfunction "10_10") (pintype "passive"))
    )
    (net (code "289") (name "unconnected-(USB1-Pad2)") (class "Default")
      (node (ref "USB1") (pin "2") (pinfunction "2_2") (pintype "passive"))
    )
    (net (code "290") (name "unconnected-(USB1-Pad3)") (class "Default")
      (node (ref "USB1") (pin "3") (pinfunction "3_3") (pintype "passive"))
    )
    (net (code "291") (name "unconnected-(USB1-Pad4)") (class "Default")
      (node (ref "USB1") (pin "4") (pinfunction "4_4") (pintype "passive"))
    )
  )
)
